# xmos_avb_brd_V4.net
KiCad netlist of a schematic drawn in EAGLE
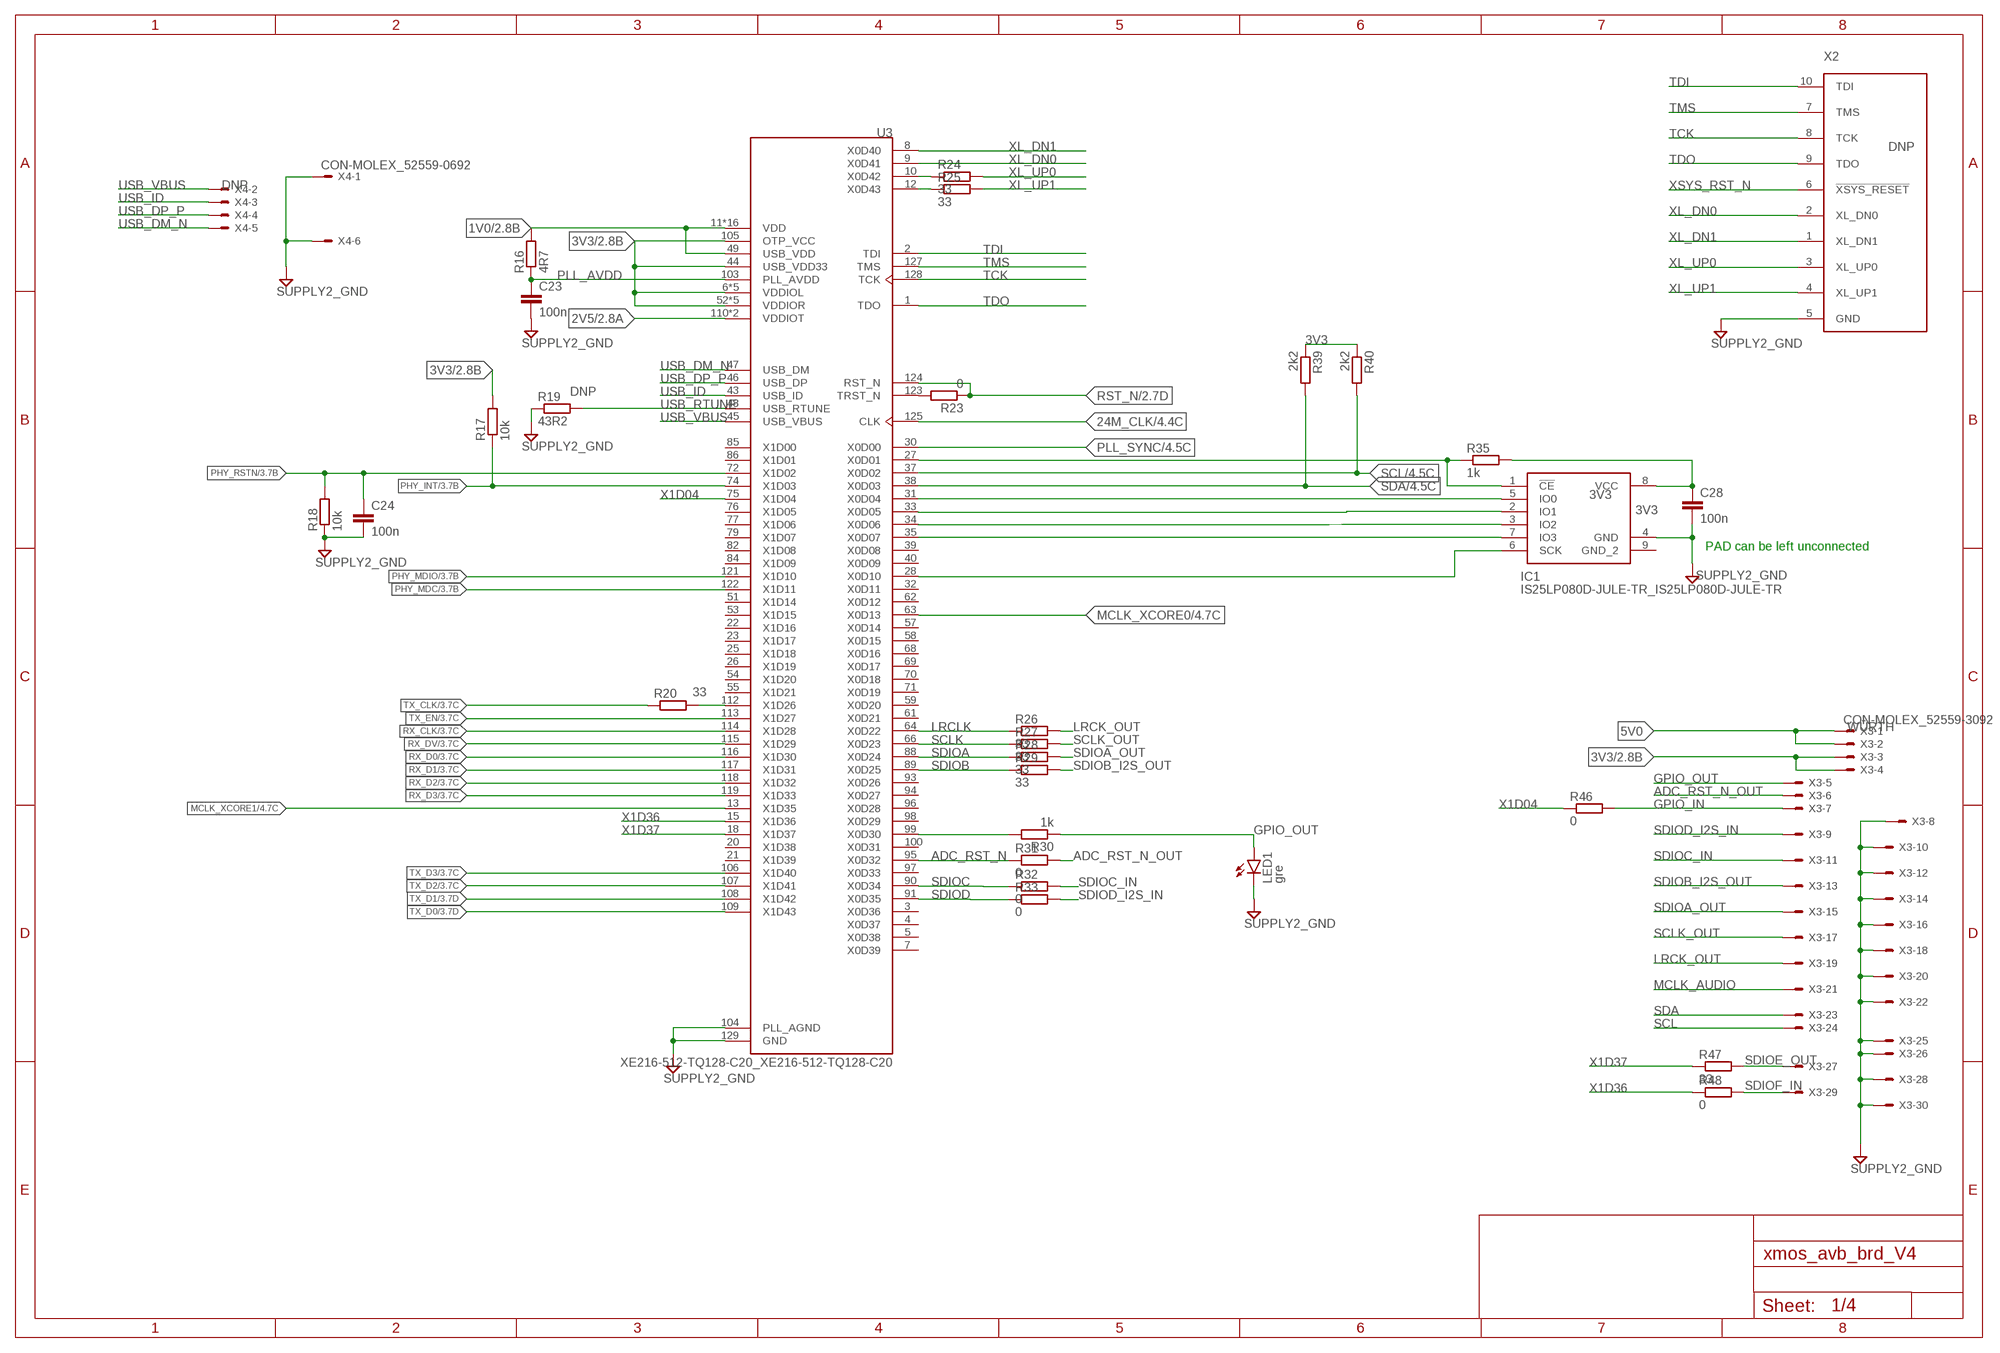
[diagram p0: schematic, sheet 1]
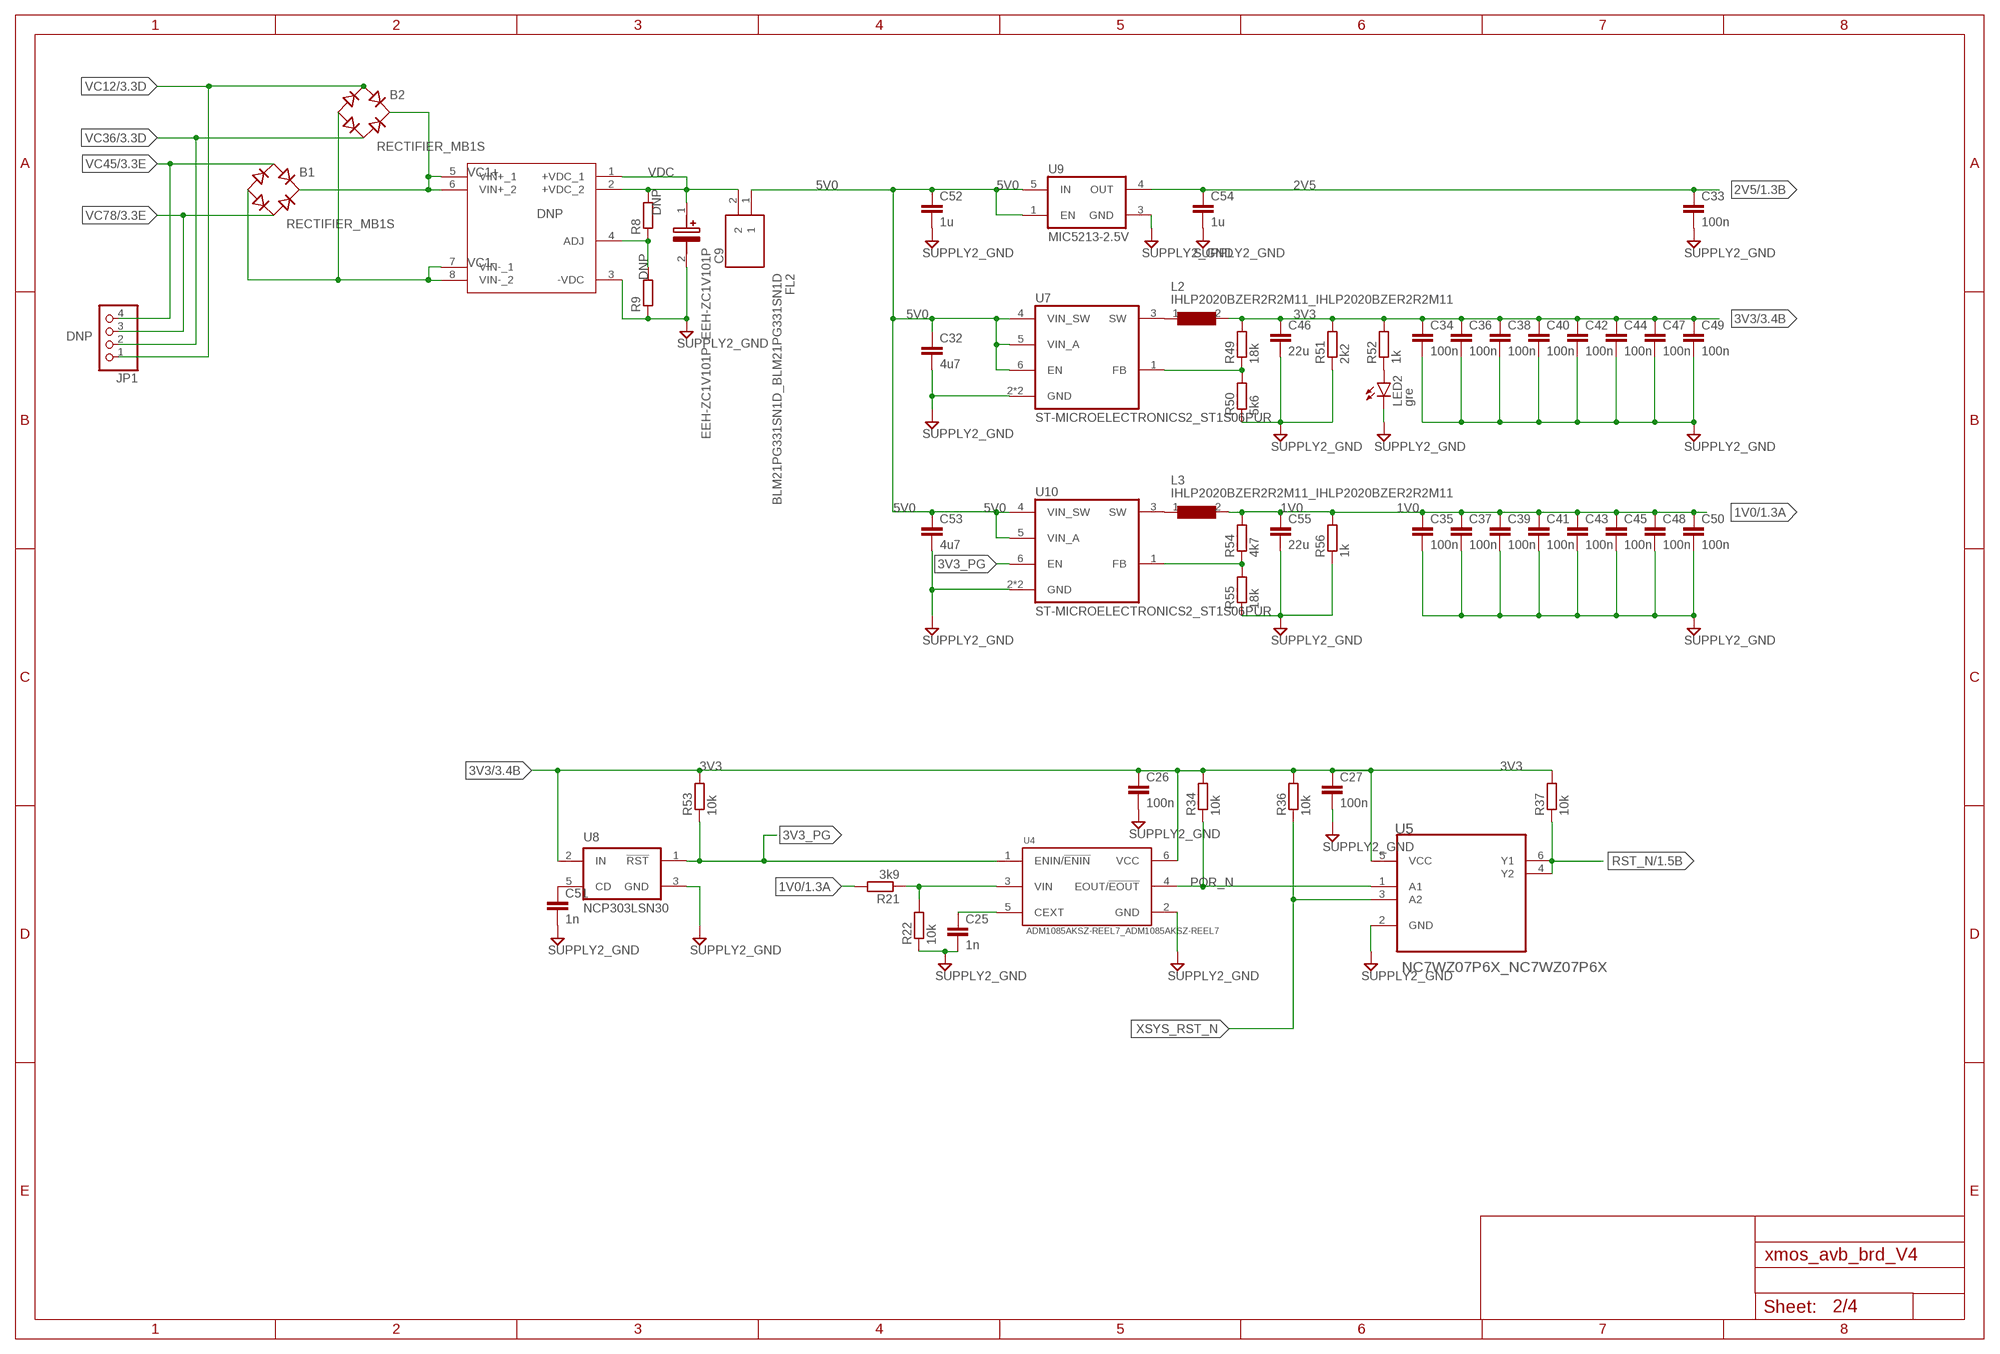
[diagram p1: schematic, sheet 2]
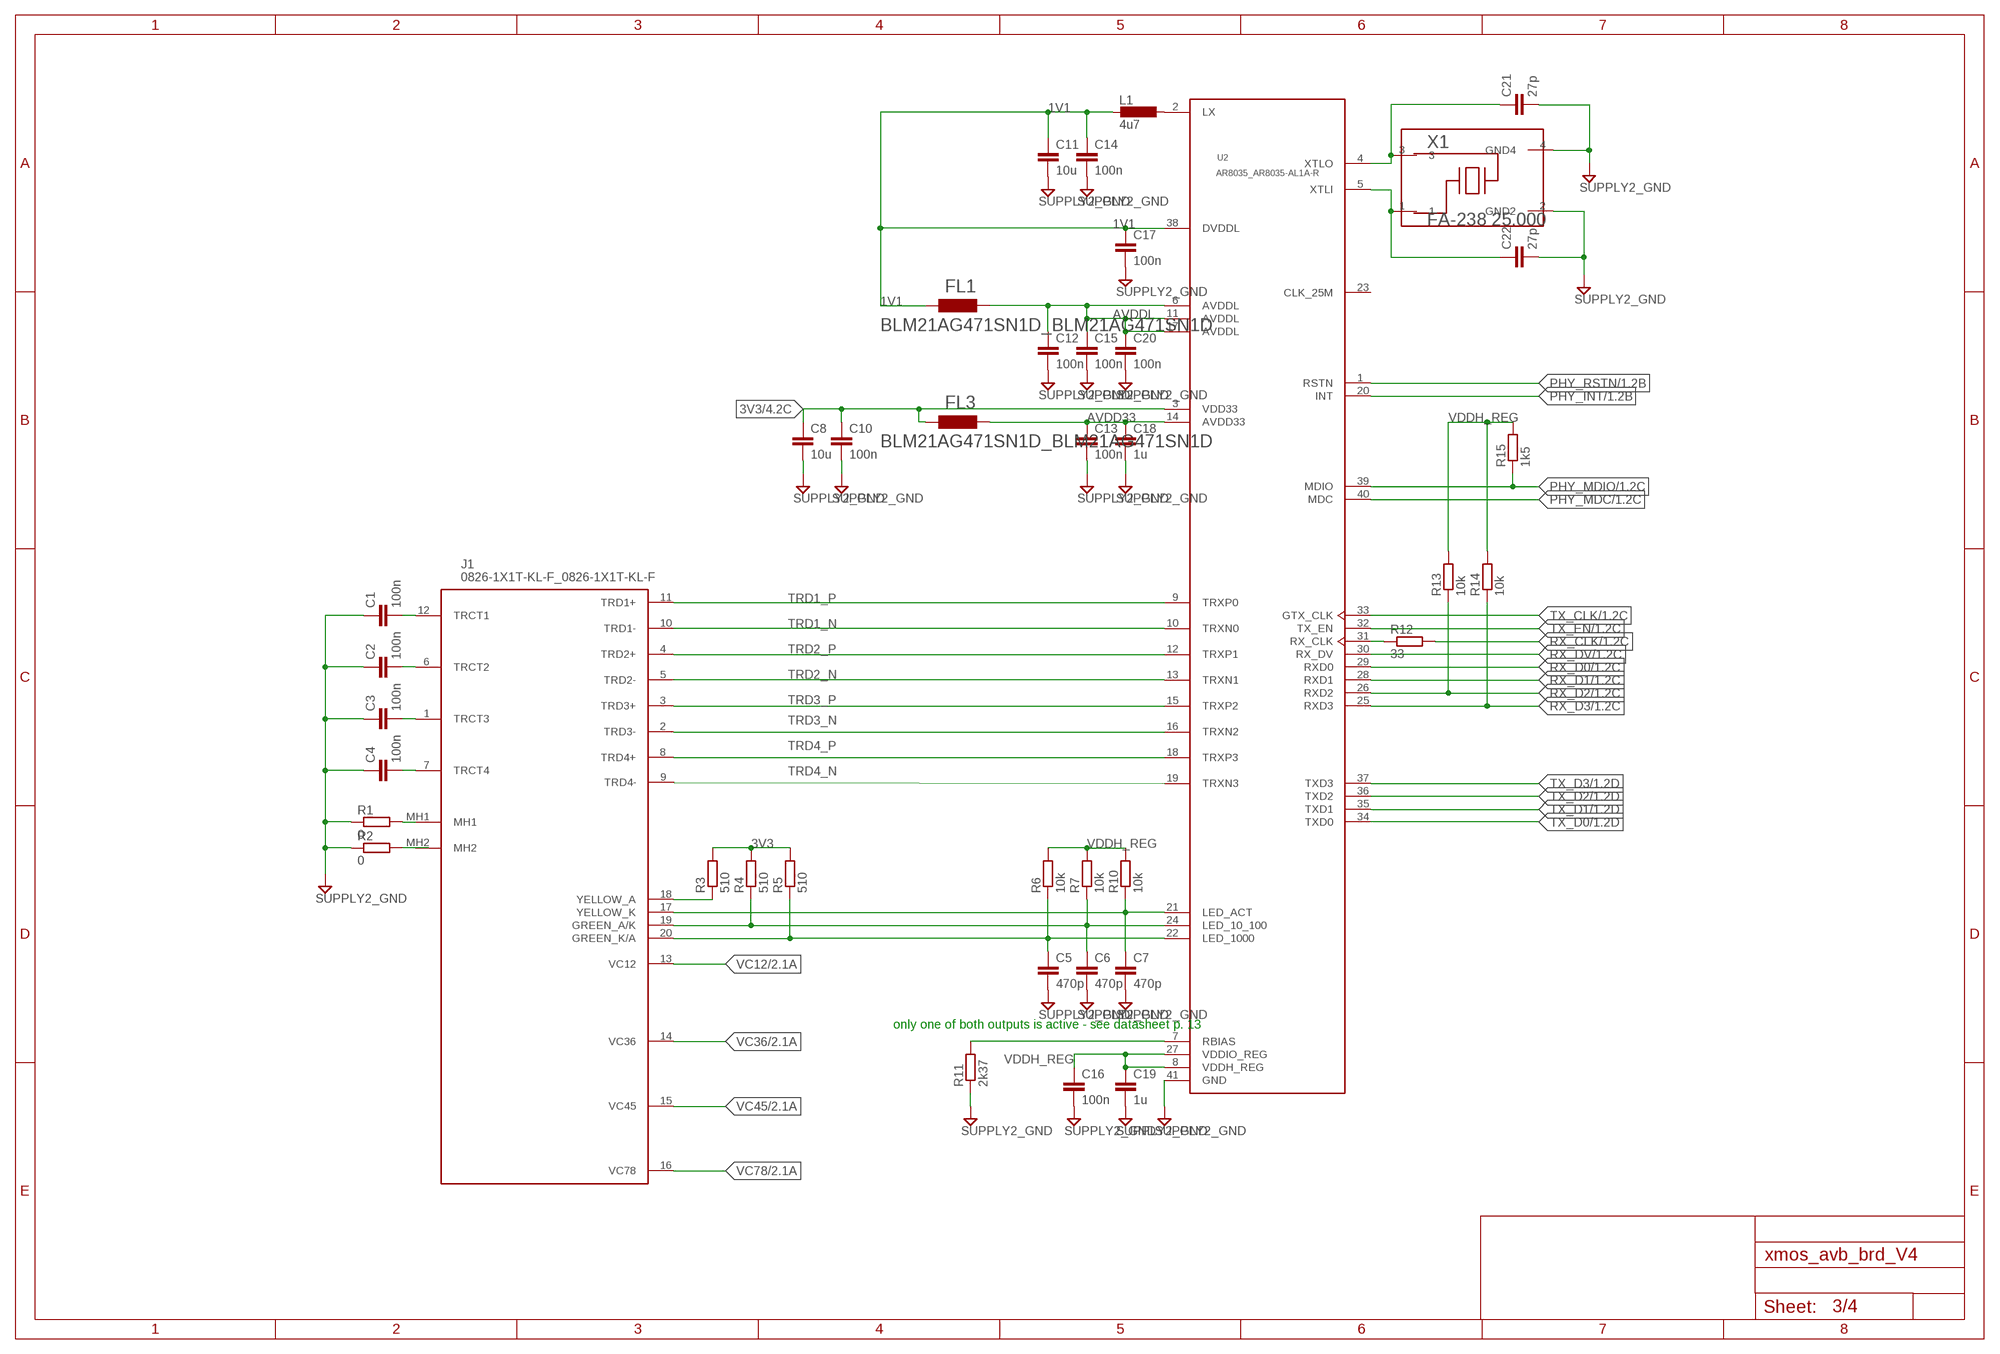
[diagram p2: schematic, sheet 3]
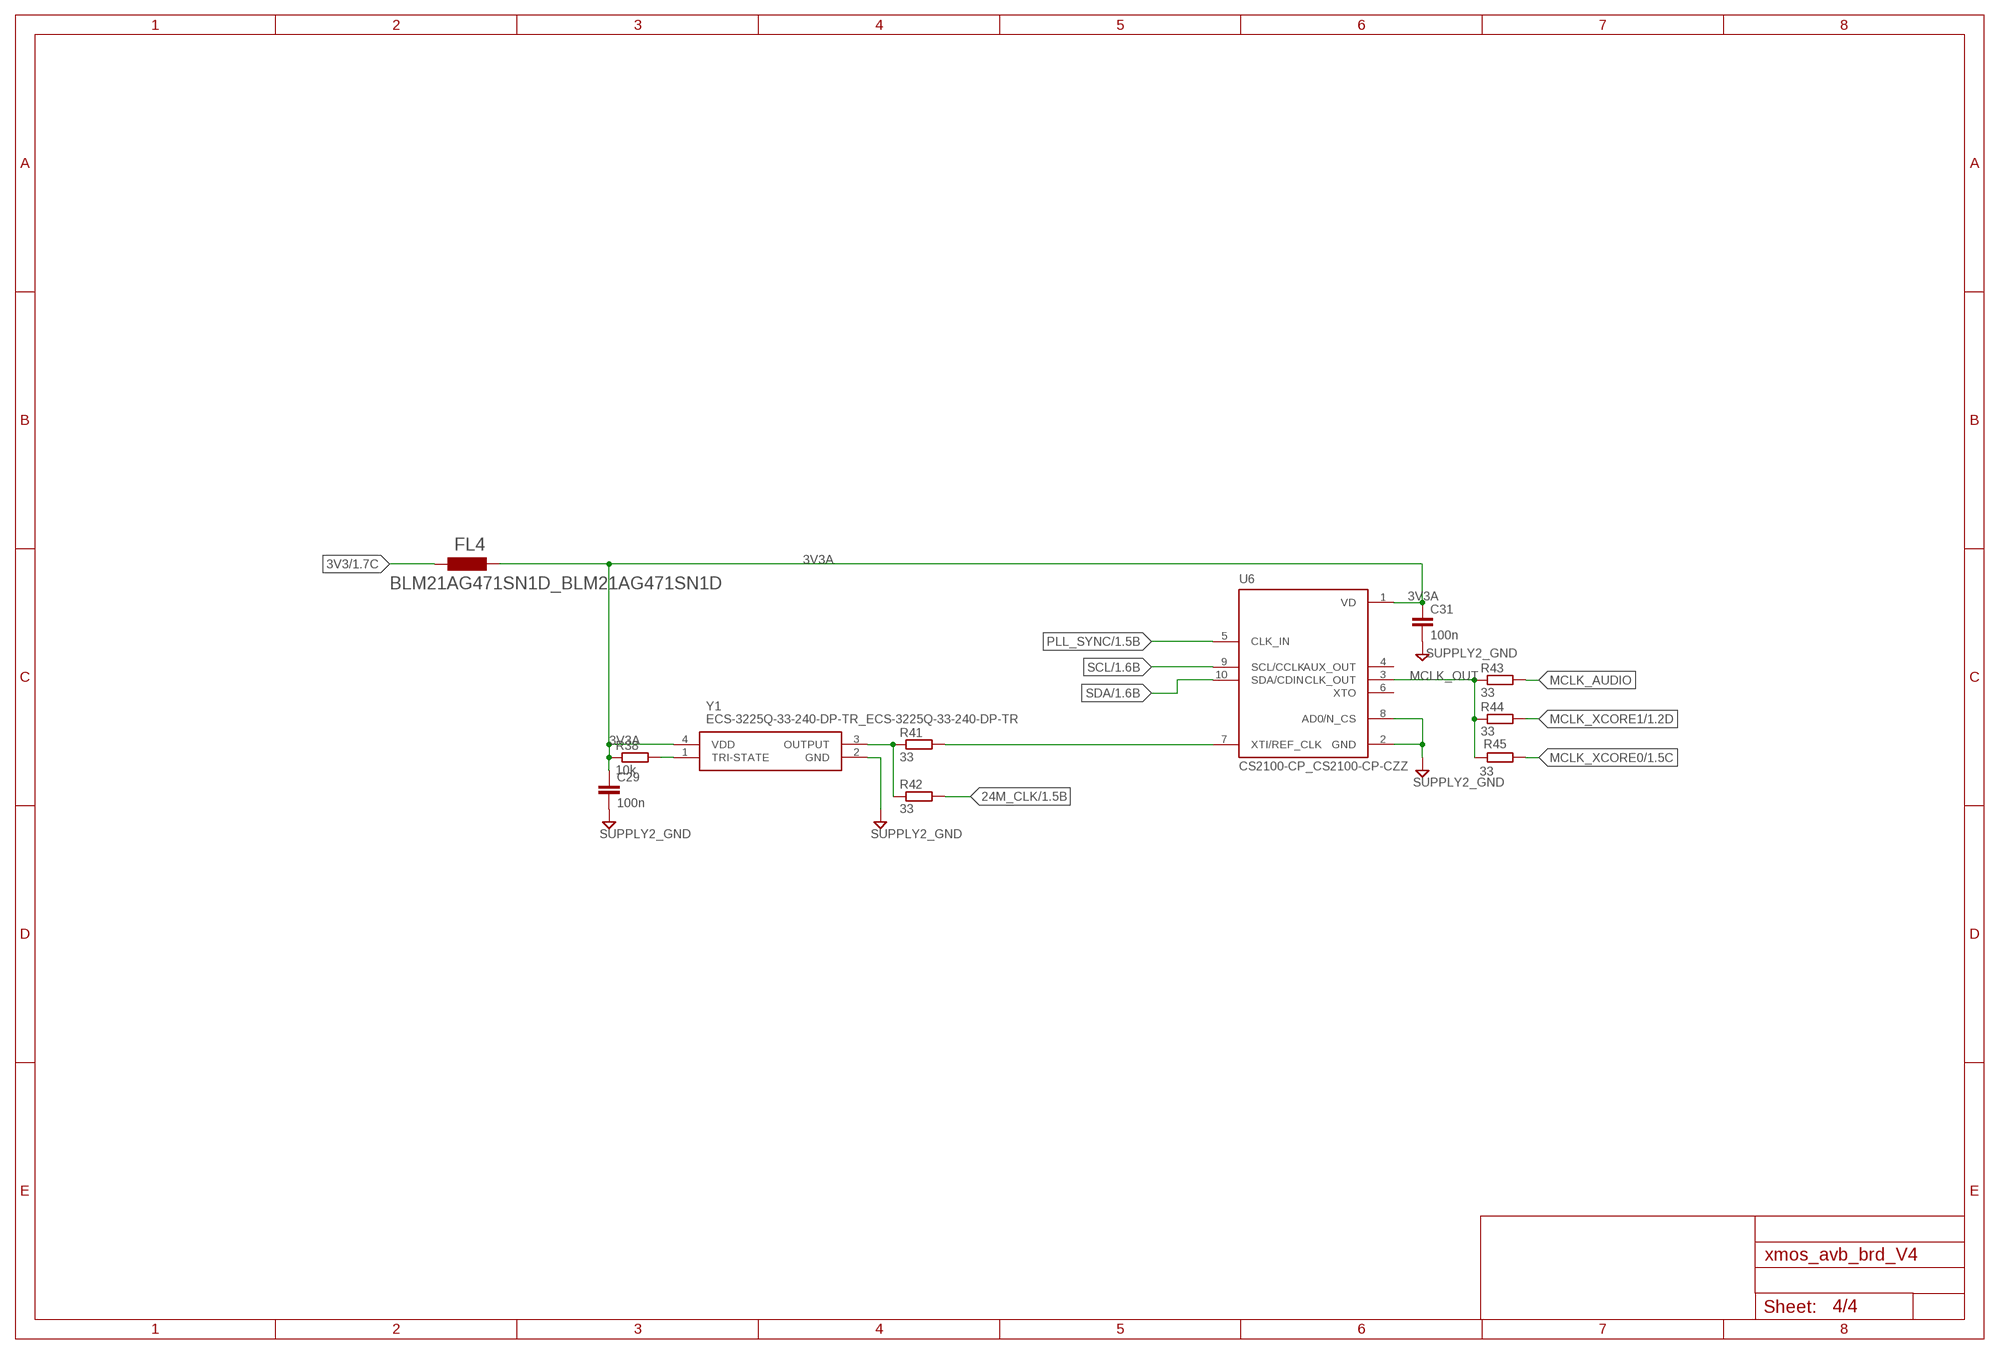
[diagram p3: schematic, sheet 4]

(export (version "E")
  (design (tool "Eeschema 10.0.6"))
  (components
    (comp (ref "C29")
      (value "100n")
      (footprint "eagle-import:RCL_C0402")
      (libsource (lib "eagle-import") (part "RCL_C-EUC0402"))
    )
    (comp (ref "C31")
      (value "100n")
      (footprint "eagle-import:RCL_C0402")
      (libsource (lib "eagle-import") (part "RCL_C-EUC0402"))
    )
    (comp (ref "FL4")
      (value "BLM21AG471SN1D_BLM21AG471SN1D")
      (footprint "eagle-import:BLM21AG471SN1D_BEADC2012X105N")
      (fields (field (name "MF") "Murata Electronics") (field (name "MP") "BLM21AG471SN1D"))
      (libsource (lib "eagle-import") (part "BLM21AG471SN1D_BLM21AG471SN1D"))
    )
    (comp (ref "R38")
      (value "10k")
      (footprint "eagle-import:RCL_R0402")
      (libsource (lib "eagle-import") (part "RCL_R-EU_R0402"))
    )
    (comp (ref "R41")
      (value "33")
      (footprint "eagle-import:RCL_R0402")
      (libsource (lib "eagle-import") (part "RCL_R-EU_R0402"))
    )
    (comp (ref "R42")
      (value "33")
      (footprint "eagle-import:RCL_R0402")
      (libsource (lib "eagle-import") (part "RCL_R-EU_R0402"))
    )
    (comp (ref "R43")
      (value "33")
      (footprint "eagle-import:RCL_R0402")
      (libsource (lib "eagle-import") (part "RCL_R-EU_R0402"))
    )
    (comp (ref "R44")
      (value "33")
      (footprint "eagle-import:RCL_R0402")
      (libsource (lib "eagle-import") (part "RCL_R-EU_R0402"))
    )
    (comp (ref "R45")
      (value "33")
      (footprint "eagle-import:RCL_R0402")
      (libsource (lib "eagle-import") (part "RCL_R-EU_R0402"))
    )
    (comp (ref "U6")
      (value "CS2100-CP_CS2100-CP-CZZ")
      (footprint "eagle-import:CS2100-CP_CIRRUS-LOGIC_MSOP10")
      (libsource (lib "eagle-import") (part "CS2100-CP_CS2100-CP-CZZ"))
    )
    (comp (ref "Y1")
      (value "ECS-3225Q-33-240-DP-TR_ECS-3225Q-33-240-DP-TR")
      (footprint "eagle-import:ECS-3225Q-33-240-DP-TR_ECS3225Q33240DPTR")
      (fields
        (field (name "MANUFACTURER_PART_NUMBER") "ECS-3225Q-33-240-DP-TR")
        (field (name "MOUSER_PART_NUMBER") "520-3225Q-33-240-DPT")
      )
      (libsource (lib "eagle-import") (part "ECS-3225Q-33-240-DP-TR_ECS-3225Q-33-240-DP-TR"))
    )
    (comp (ref "B1")
      (value "RECTIFIER_MB1S")
      (footprint "eagle-import:RECTIFIER_SOIC-4")
      (libsource (lib "eagle-import") (part "RECTIFIER_MBS1"))
    )
    (comp (ref "B2")
      (value "RECTIFIER_MB1S")
      (footprint "eagle-import:RECTIFIER_SOIC-4")
      (libsource (lib "eagle-import") (part "RECTIFIER_MBS1"))
    )
    (comp (ref "C9")
      (value "EEH-ZC1V101P_EEH-ZC1V101P")
      (footprint "eagle-import:EEH-ZC1V101P_CAPAE830X1050N")
      (fields
        (field (name "MANUFACTURER_PART_NUMBER") "EEH-ZC1V101P")
        (field (name "MOUSER_PART_NUMBER") "667-EEH-ZC1V101P")
      )
      (libsource (lib "eagle-import") (part "EEH-ZC1V101P_EEH-ZC1V101P"))
    )
    (comp (ref "C25")
      (value "1n")
      (footprint "eagle-import:RCL_C0402")
      (libsource (lib "eagle-import") (part "RCL_C-EUC0402"))
    )
    (comp (ref "C26")
      (value "100n")
      (footprint "eagle-import:RCL_C0402")
      (libsource (lib "eagle-import") (part "RCL_C-EUC0402"))
    )
    (comp (ref "C27")
      (value "100n")
      (footprint "eagle-import:RCL_C0402")
      (libsource (lib "eagle-import") (part "RCL_C-EUC0402"))
    )
    (comp (ref "C32")
      (value "4u7")
      (footprint "eagle-import:RCL_C1206")
      (libsource (lib "eagle-import") (part "RCL_C-EUC1206"))
    )
    (comp (ref "C33")
      (value "100n")
      (footprint "eagle-import:RCL_C0402")
      (libsource (lib "eagle-import") (part "RCL_C-EUC0402"))
    )
    (comp (ref "C34")
      (value "100n")
      (footprint "eagle-import:RCL_C0402")
      (libsource (lib "eagle-import") (part "RCL_C-EUC0402"))
    )
    (comp (ref "C35")
      (value "100n")
      (footprint "eagle-import:RCL_C0402")
      (libsource (lib "eagle-import") (part "RCL_C-EUC0402"))
    )
    (comp (ref "C36")
      (value "100n")
      (footprint "eagle-import:RCL_C0402")
      (libsource (lib "eagle-import") (part "RCL_C-EUC0402"))
    )
    (comp (ref "C37")
      (value "100n")
      (footprint "eagle-import:RCL_C0402")
      (libsource (lib "eagle-import") (part "RCL_C-EUC0402"))
    )
    (comp (ref "C38")
      (value "100n")
      (footprint "eagle-import:RCL_C0402")
      (libsource (lib "eagle-import") (part "RCL_C-EUC0402"))
    )
    (comp (ref "C39")
      (value "100n")
      (footprint "eagle-import:RCL_C0402")
      (libsource (lib "eagle-import") (part "RCL_C-EUC0402"))
    )
    (comp (ref "C40")
      (value "100n")
      (footprint "eagle-import:RCL_C0402")
      (libsource (lib "eagle-import") (part "RCL_C-EUC0402"))
    )
    (comp (ref "C41")
      (value "100n")
      (footprint "eagle-import:RCL_C0402")
      (libsource (lib "eagle-import") (part "RCL_C-EUC0402"))
    )
    (comp (ref "C42")
      (value "100n")
      (footprint "eagle-import:RCL_C0402")
      (libsource (lib "eagle-import") (part "RCL_C-EUC0402"))
    )
    (comp (ref "C43")
      (value "100n")
      (footprint "eagle-import:RCL_C0402")
      (libsource (lib "eagle-import") (part "RCL_C-EUC0402"))
    )
    (comp (ref "C44")
      (value "100n")
      (footprint "eagle-import:RCL_C0402")
      (libsource (lib "eagle-import") (part "RCL_C-EUC0402"))
    )
    (comp (ref "C45")
      (value "100n")
      (footprint "eagle-import:RCL_C0402")
      (libsource (lib "eagle-import") (part "RCL_C-EUC0402"))
    )
    (comp (ref "C46")
      (value "22u")
      (footprint "eagle-import:RCL_C1206")
      (libsource (lib "eagle-import") (part "RCL_C-EUC1206"))
    )
    (comp (ref "C47")
      (value "100n")
      (footprint "eagle-import:RCL_C0402")
      (libsource (lib "eagle-import") (part "RCL_C-EUC0402"))
    )
    (comp (ref "C48")
      (value "100n")
      (footprint "eagle-import:RCL_C0402")
      (libsource (lib "eagle-import") (part "RCL_C-EUC0402"))
    )
    (comp (ref "C49")
      (value "100n")
      (footprint "eagle-import:RCL_C0402")
      (libsource (lib "eagle-import") (part "RCL_C-EUC0402"))
    )
    (comp (ref "C50")
      (value "100n")
      (footprint "eagle-import:RCL_C0402")
      (libsource (lib "eagle-import") (part "RCL_C-EUC0402"))
    )
    (comp (ref "C51")
      (value "1n")
      (footprint "eagle-import:RCL_C0402")
      (libsource (lib "eagle-import") (part "RCL_C-EUC0402"))
    )
    (comp (ref "C52")
      (value "1u")
      (footprint "eagle-import:RCL_C1206")
      (libsource (lib "eagle-import") (part "RCL_C-EUC1206"))
    )
    (comp (ref "C53")
      (value "4u7")
      (footprint "eagle-import:RCL_C1206")
      (libsource (lib "eagle-import") (part "RCL_C-EUC1206"))
    )
    (comp (ref "C54")
      (value "1u")
      (footprint "eagle-import:RCL_C1206")
      (libsource (lib "eagle-import") (part "RCL_C-EUC1206"))
    )
    (comp (ref "C55")
      (value "22u")
      (footprint "eagle-import:RCL_C1206")
      (libsource (lib "eagle-import") (part "RCL_C-EUC1206"))
    )
    (comp (ref "FL2")
      (value "BLM21PG331SN1D_BLM21PG331SN1D")
      (footprint "eagle-import:BLM21PG331SN1D_BEADC2012X105N")
      (fields
        (field (name "MANUFACTURER_PART_NUMBER") "BLM21PG331SN1D")
        (field (name "MOUSER_PART_NUMBER") "81-BLM21P331SG")
      )
      (libsource (lib "eagle-import") (part "BLM21PG331SN1D_BLM21PG331SN1D"))
    )
    (comp (ref "JP1")
      (value "PINHEAD_PINHD-1X4")
      (footprint "eagle-import:PINHEAD_1X04")
      (fields (field (name "DNP") "DNP"))
      (libsource (lib "eagle-import") (part "PINHEAD_PINHD-1X4"))
    )
    (comp (ref "L2")
      (value "IHLP2020BZER2R2M11_IHLP2020BZER2R2M11")
      (footprint "eagle-import:IHLP2020BZER2R2M11_INDPM5552X200N")
      (fields
        (field (name "MANUFACTURER_PART_NUMBER") "IHLP2020BZER2R2M11")
        (field (name "MOUSER_PART_NUMBER") "70-IHLP2020BZER2R2M1")
      )
      (libsource (lib "eagle-import") (part "IHLP2020BZER2R2M11_IHLP2020BZER2R2M11"))
    )
    (comp (ref "L3")
      (value "IHLP2020BZER2R2M11_IHLP2020BZER2R2M11")
      (footprint "eagle-import:IHLP2020BZER2R2M11_INDPM5552X200N")
      (fields
        (field (name "MANUFACTURER_PART_NUMBER") "IHLP2020BZER2R2M11")
        (field (name "MOUSER_PART_NUMBER") "70-IHLP2020BZER2R2M1")
      )
      (libsource (lib "eagle-import") (part "IHLP2020BZER2R2M11_IHLP2020BZER2R2M11"))
    )
    (comp (ref "LED2")
      (value "gre")
      (footprint "eagle-import:LED_CHIP-LED0603")
      (libsource (lib "eagle-import") (part "LED_LEDCHIP-LED0603"))
    )
    (comp (ref "R8")
      (value "RCL_R-EU_R0402")
      (footprint "eagle-import:RCL_R0402")
      (fields (field (name "DNP") "DNP"))
      (libsource (lib "eagle-import") (part "RCL_R-EU_R0402"))
    )
    (comp (ref "R9")
      (value "RCL_R-EU_R0402")
      (footprint "eagle-import:RCL_R0402")
      (fields (field (name "DNP") "DNP"))
      (libsource (lib "eagle-import") (part "RCL_R-EU_R0402"))
    )
    (comp (ref "R21")
      (value "3k9")
      (footprint "eagle-import:RCL_R0402")
      (libsource (lib "eagle-import") (part "RCL_R-EU_R0402"))
    )
    (comp (ref "R22")
      (value "10k")
      (footprint "eagle-import:RCL_R0402")
      (libsource (lib "eagle-import") (part "RCL_R-EU_R0402"))
    )
    (comp (ref "R34")
      (value "10k")
      (footprint "eagle-import:RCL_R0402")
      (libsource (lib "eagle-import") (part "RCL_R-EU_R0402"))
    )
    (comp (ref "R36")
      (value "10k")
      (footprint "eagle-import:RCL_R0402")
      (libsource (lib "eagle-import") (part "RCL_R-EU_R0402"))
    )
    (comp (ref "R37")
      (value "10k")
      (footprint "eagle-import:RCL_R0402")
      (libsource (lib "eagle-import") (part "RCL_R-EU_R0402"))
    )
    (comp (ref "R49")
      (value "18k")
      (footprint "eagle-import:RCL_R0402")
      (libsource (lib "eagle-import") (part "RCL_R-EU_R0402"))
    )
    (comp (ref "R50")
      (value "5k6")
      (footprint "eagle-import:RCL_R0402")
      (libsource (lib "eagle-import") (part "RCL_R-EU_R0402"))
    )
    (comp (ref "R51")
      (value "2k2")
      (footprint "eagle-import:RCL_R0402")
      (libsource (lib "eagle-import") (part "RCL_R-EU_R0402"))
    )
    (comp (ref "R52")
      (value "1k")
      (footprint "eagle-import:RCL_R0402")
      (libsource (lib "eagle-import") (part "RCL_R-EU_R0402"))
    )
    (comp (ref "R53")
      (value "10k")
      (footprint "eagle-import:RCL_R0402")
      (libsource (lib "eagle-import") (part "RCL_R-EU_R0402"))
    )
    (comp (ref "R54")
      (value "4k7")
      (footprint "eagle-import:RCL_R0402")
      (libsource (lib "eagle-import") (part "RCL_R-EU_R0402"))
    )
    (comp (ref "R55")
      (value "18k")
      (footprint "eagle-import:RCL_R0402")
      (libsource (lib "eagle-import") (part "RCL_R-EU_R0402"))
    )
    (comp (ref "R56")
      (value "1k")
      (footprint "eagle-import:RCL_R0402")
      (libsource (lib "eagle-import") (part "RCL_R-EU_R0402"))
    )
    (comp (ref "U1")
      (value "AG9900_AG9905LP")
      (footprint "eagle-import:AG9900_AG9900LP")
      (fields (field (name "MF") "Silvertel") (field (name "MP") "AG9905LP") (field (name "DNP") "DNP"))
      (libsource (lib "eagle-import") (part "AG9900_AG9905LP"))
    )
    (comp (ref "U4")
      (value "ADM1085AKSZ-REEL7_ADM1085AKSZ-REEL7")
      (footprint "eagle-import:ADM1085AKSZ-REEL7_SOP65P210X95-6N")
      (fields (field (name "MF") "Analog Devices") (field (name "MP") "ADM1085AKSZ-REEL7"))
      (libsource (lib "eagle-import") (part "ADM1085AKSZ-REEL7_ADM1085AKSZ-REEL7"))
    )
    (comp (ref "U5")
      (value "NC7WZ07P6X_NC7WZ07P6X")
      (footprint "eagle-import:NC7WZ07P6X_SOT65P210X110-6N")
      (fields (field (name "MF") "ON Semiconductor") (field (name "MP") "NC7WZ07P6X"))
      (libsource (lib "eagle-import") (part "NC7WZ07P6X_NC7WZ07P6X"))
    )
    (comp (ref "U7")
      (value "ST-MICROELECTRONICS2_ST1S06PUR")
      (footprint "eagle-import:ST-MICROELECTRONICS2_DFN6")
      (libsource (lib "eagle-import") (part "ST-MICROELECTRONICS2_ST1S06PUR"))
    )
    (comp (ref "U8")
      (value "NCP303LSN30")
      (footprint "eagle-import:ON-SEMI_SOT23-5")
      (libsource (lib "eagle-import") (part "ON-SEMI_NCP303"))
    )
    (comp (ref "U9")
      (value "MIC5213-2.5V")
      (footprint "eagle-import:MICREL2_SC70-5")
      (libsource (lib "eagle-import") (part "MICREL2_MIC5213"))
    )
    (comp (ref "U10")
      (value "ST-MICROELECTRONICS2_ST1S06PUR")
      (footprint "eagle-import:ST-MICROELECTRONICS2_DFN6")
      (libsource (lib "eagle-import") (part "ST-MICROELECTRONICS2_ST1S06PUR"))
    )
    (comp (ref "C1")
      (value "100n")
      (footprint "eagle-import:RCL_C0402")
      (libsource (lib "eagle-import") (part "RCL_C-EUC0402"))
    )
    (comp (ref "C2")
      (value "100n")
      (footprint "eagle-import:RCL_C0402")
      (libsource (lib "eagle-import") (part "RCL_C-EUC0402"))
    )
    (comp (ref "C3")
      (value "100n")
      (footprint "eagle-import:RCL_C0402")
      (libsource (lib "eagle-import") (part "RCL_C-EUC0402"))
    )
    (comp (ref "C4")
      (value "100n")
      (footprint "eagle-import:RCL_C0402")
      (libsource (lib "eagle-import") (part "RCL_C-EUC0402"))
    )
    (comp (ref "C5")
      (value "470p")
      (footprint "eagle-import:RCL_C0402")
      (libsource (lib "eagle-import") (part "RCL_C-EUC0402"))
    )
    (comp (ref "C6")
      (value "470p")
      (footprint "eagle-import:RCL_C0402")
      (libsource (lib "eagle-import") (part "RCL_C-EUC0402"))
    )
    (comp (ref "C7")
      (value "470p")
      (footprint "eagle-import:RCL_C0402")
      (libsource (lib "eagle-import") (part "RCL_C-EUC0402"))
    )
    (comp (ref "C8")
      (value "10u")
      (footprint "eagle-import:RCL_C1206")
      (libsource (lib "eagle-import") (part "RCL_C-EUC1206"))
    )
    (comp (ref "C10")
      (value "100n")
      (footprint "eagle-import:RCL_C0402")
      (libsource (lib "eagle-import") (part "RCL_C-EUC0402"))
    )
    (comp (ref "C11")
      (value "10u")
      (footprint "eagle-import:RCL_C1206")
      (libsource (lib "eagle-import") (part "RCL_C-EUC1206"))
    )
    (comp (ref "C12")
      (value "100n")
      (footprint "eagle-import:RCL_C0402")
      (libsource (lib "eagle-import") (part "RCL_C-EUC0402"))
    )
    (comp (ref "C13")
      (value "100n")
      (footprint "eagle-import:RCL_C0402")
      (libsource (lib "eagle-import") (part "RCL_C-EUC0402"))
    )
    (comp (ref "C14")
      (value "100n")
      (footprint "eagle-import:RCL_C0402")
      (libsource (lib "eagle-import") (part "RCL_C-EUC0402"))
    )
    (comp (ref "C15")
      (value "100n")
      (footprint "eagle-import:RCL_C0402")
      (libsource (lib "eagle-import") (part "RCL_C-EUC0402"))
    )
    (comp (ref "C16")
      (value "100n")
      (footprint "eagle-import:RCL_C0402")
      (libsource (lib "eagle-import") (part "RCL_C-EUC0402"))
    )
    (comp (ref "C17")
      (value "100n")
      (footprint "eagle-import:RCL_C0402")
      (libsource (lib "eagle-import") (part "RCL_C-EUC0402"))
    )
    (comp (ref "C18")
      (value "1u")
      (footprint "eagle-import:RCL_C1206")
      (libsource (lib "eagle-import") (part "RCL_C-EUC1206"))
    )
    (comp (ref "C19")
      (value "1u")
      (footprint "eagle-import:RCL_C1206")
      (libsource (lib "eagle-import") (part "RCL_C-EUC1206"))
    )
    (comp (ref "C20")
      (value "100n")
      (footprint "eagle-import:RCL_C0402")
      (libsource (lib "eagle-import") (part "RCL_C-EUC0402"))
    )
    (comp (ref "C21")
      (value "27p")
      (footprint "eagle-import:RCL_C0402")
      (libsource (lib "eagle-import") (part "RCL_C-EUC0402"))
    )
    (comp (ref "C22")
      (value "27p")
      (footprint "eagle-import:RCL_C0402")
      (libsource (lib "eagle-import") (part "RCL_C-EUC0402"))
    )
    (comp (ref "FL1")
      (value "BLM21AG471SN1D_BLM21AG471SN1D")
      (footprint "eagle-import:BLM21AG471SN1D_BEADC2012X105N")
      (fields (field (name "MF") "Murata Electronics") (field (name "MP") "BLM21AG471SN1D"))
      (libsource (lib "eagle-import") (part "BLM21AG471SN1D_BLM21AG471SN1D"))
    )
    (comp (ref "FL3")
      (value "BLM21AG471SN1D_BLM21AG471SN1D")
      (footprint "eagle-import:BLM21AG471SN1D_BEADC2012X105N")
      (fields (field (name "MF") "Murata Electronics") (field (name "MP") "BLM21AG471SN1D"))
      (libsource (lib "eagle-import") (part "BLM21AG471SN1D_BLM21AG471SN1D"))
    )
    (comp (ref "J1")
      (value "0826-1X1T-KL-F_0826-1X1T-KL-F")
      (footprint "eagle-import:0826-1X1T-KL-F_08261X1TKLF")
      (fields
        (field (name "MANUFACTURER_PART_NUMBER") "0826-1X1T-KL-F")
        (field (name "MOUSER_PART_NUMBER") "530-0826-1X1T-KL-F")
      )
      (libsource (lib "eagle-import") (part "0826-1X1T-KL-F_0826-1X1T-KL-F"))
    )
    (comp (ref "L1")
      (value "4u7")
      (footprint "eagle-import:RCL_L2012C")
      (libsource (lib "eagle-import") (part "RCL_L-EUL2012C"))
    )
    (comp (ref "R1")
      (value "0")
      (footprint "eagle-import:RCL_R0402")
      (libsource (lib "eagle-import") (part "RCL_R-EU_R0402"))
    )
    (comp (ref "R2")
      (value "0")
      (footprint "eagle-import:RCL_R0402")
      (libsource (lib "eagle-import") (part "RCL_R-EU_R0402"))
    )
    (comp (ref "R3")
      (value "510")
      (footprint "eagle-import:RCL_R0402")
      (libsource (lib "eagle-import") (part "RCL_R-EU_R0402"))
    )
    (comp (ref "R4")
      (value "510")
      (footprint "eagle-import:RCL_R0402")
      (libsource (lib "eagle-import") (part "RCL_R-EU_R0402"))
    )
    (comp (ref "R5")
      (value "510")
      (footprint "eagle-import:RCL_R0402")
      (libsource (lib "eagle-import") (part "RCL_R-EU_R0402"))
    )
    (comp (ref "R6")
      (value "10k")
      (footprint "eagle-import:RCL_R0402")
      (libsource (lib "eagle-import") (part "RCL_R-EU_R0402"))
    )
    (comp (ref "R7")
      (value "10k")
      (footprint "eagle-import:RCL_R0402")
      (libsource (lib "eagle-import") (part "RCL_R-EU_R0402"))
    )
    (comp (ref "R10")
      (value "10k")
      (footprint "eagle-import:RCL_R0402")
      (libsource (lib "eagle-import") (part "RCL_R-EU_R0402"))
    )
    (comp (ref "R11")
      (value "2k37")
      (footprint "eagle-import:RCL_R0402")
      (libsource (lib "eagle-import") (part "RCL_R-EU_R0402"))
    )
    (comp (ref "R12")
      (value "33")
      (footprint "eagle-import:RCL_R0402")
      (libsource (lib "eagle-import") (part "RCL_R-EU_R0402"))
    )
    (comp (ref "R13")
      (value "10k")
      (footprint "eagle-import:RCL_R0402")
      (libsource (lib "eagle-import") (part "RCL_R-EU_R0402"))
    )
    (comp (ref "R14")
      (value "10k")
      (footprint "eagle-import:RCL_R0402")
      (libsource (lib "eagle-import") (part "RCL_R-EU_R0402"))
    )
    (comp (ref "R15")
      (value "1k5")
      (footprint "eagle-import:RCL_R0402")
      (libsource (lib "eagle-import") (part "RCL_R-EU_R0402"))
    )
    (comp (ref "U2")
      (value "AR8035_AR8035-AL1A-R")
      (footprint "eagle-import:AR8035_QFN40P500X500X75-41N")
      (fields (field (name "MF") "Qualcomm") (field (name "MP") "AR8035-AL1A-R"))
      (libsource (lib "eagle-import") (part "AR8035_AR8035-AL1A-R"))
    )
    (comp (ref "X1")
      (value "FA-238 25.000")
      (footprint "eagle-import:FA-238_OSCCC320X250X70-4N")
      (fields
        (field (name "MANUFACTURER_PART_NUMBER") "FA-238 25.0000MB-C3 ")
        (field (name "MF") "Epson")
        (field (name "MP") "FA-238")
      )
      (libsource (lib "eagle-import") (part "FA-238_FA-238"))
    )
    (comp (ref "C23")
      (value "100n")
      (footprint "eagle-import:RCL_C0402")
      (libsource (lib "eagle-import") (part "RCL_C-EUC0402"))
    )
    (comp (ref "C24")
      (value "100n")
      (footprint "eagle-import:RCL_C0402")
      (libsource (lib "eagle-import") (part "RCL_C-EUC0402"))
    )
    (comp (ref "C28")
      (value "100n")
      (footprint "eagle-import:RCL_C0402")
      (libsource (lib "eagle-import") (part "RCL_C-EUC0402"))
    )
    (comp (ref "IC1")
      (value "IS25LP080D-JULE-TR_IS25LP080D-JULE-TR")
      (footprint "eagle-import:IS25LP080D-JULE-TR_SON50P300X200X55-9N")
      (fields (field (name "MANUFACTURER_PART_NUMBER") "IS25LP080D-JULE-TR"))
      (libsource (lib "eagle-import") (part "IS25LP080D-JULE-TR_IS25LP080D-JULE-TR"))
    )
    (comp (ref "LED1")
      (value "gre")
      (footprint "eagle-import:LED_CHIP-LED0603")
      (libsource (lib "eagle-import") (part "LED_LEDCHIP-LED0603"))
    )
    (comp (ref "R16")
      (value "4R7")
      (footprint "eagle-import:RCL_R0402")
      (libsource (lib "eagle-import") (part "RCL_R-EU_R0402"))
    )
    (comp (ref "R17")
      (value "10k")
      (footprint "eagle-import:RCL_R0402")
      (libsource (lib "eagle-import") (part "RCL_R-EU_R0402"))
    )
    (comp (ref "R18")
      (value "10k")
      (footprint "eagle-import:RCL_R0402")
      (libsource (lib "eagle-import") (part "RCL_R-EU_R0402"))
    )
    (comp (ref "R19")
      (value "43R2")
      (footprint "eagle-import:RCL_R0402")
      (fields (field (name "DNP") "DNP"))
      (libsource (lib "eagle-import") (part "RCL_R-EU_R0402"))
    )
    (comp (ref "R20")
      (value "33")
      (footprint "eagle-import:RCL_R0402")
      (libsource (lib "eagle-import") (part "RCL_R-EU_R0402"))
    )
    (comp (ref "R23")
      (value "0")
      (footprint "eagle-import:RCL_R0402")
      (libsource (lib "eagle-import") (part "RCL_R-EU_R0402"))
    )
    (comp (ref "R24")
      (value "33")
      (footprint "eagle-import:RCL_R0402")
      (libsource (lib "eagle-import") (part "RCL_R-EU_R0402"))
    )
    (comp (ref "R25")
      (value "33")
      (footprint "eagle-import:RCL_R0402")
      (libsource (lib "eagle-import") (part "RCL_R-EU_R0402"))
    )
    (comp (ref "R26")
      (value "33")
      (footprint "eagle-import:RCL_R0402")
      (libsource (lib "eagle-import") (part "RCL_R-EU_R0402"))
    )
    (comp (ref "R27")
      (value "33")
      (footprint "eagle-import:RCL_R0402")
      (libsource (lib "eagle-import") (part "RCL_R-EU_R0402"))
    )
    (comp (ref "R28")
      (value "33")
      (footprint "eagle-import:RCL_R0402")
      (libsource (lib "eagle-import") (part "RCL_R-EU_R0402"))
    )
    (comp (ref "R29")
      (value "33")
      (footprint "eagle-import:RCL_R0402")
      (libsource (lib "eagle-import") (part "RCL_R-EU_R0402"))
    )
    (comp (ref "R30")
      (value "1k")
      (footprint "eagle-import:RCL_R0402")
      (libsource (lib "eagle-import") (part "RCL_R-EU_R0402"))
    )
    (comp (ref "R31")
      (value "0")
      (footprint "eagle-import:RCL_R0402")
      (libsource (lib "eagle-import") (part "RCL_R-EU_R0402"))
    )
    (comp (ref "R32")
      (value "0")
      (footprint "eagle-import:RCL_R0402")
      (libsource (lib "eagle-import") (part "RCL_R-EU_R0402"))
    )
    (comp (ref "R33")
      (value "0")
      (footprint "eagle-import:RCL_R0402")
      (libsource (lib "eagle-import") (part "RCL_R-EU_R0402"))
    )
    (comp (ref "R35")
      (value "1k")
      (footprint "eagle-import:RCL_R0402")
      (libsource (lib "eagle-import") (part "RCL_R-EU_R0402"))
    )
    (comp (ref "R39")
      (value "2k2")
      (footprint "eagle-import:RCL_R0402")
      (libsource (lib "eagle-import") (part "RCL_R-EU_R0402"))
    )
    (comp (ref "R40")
      (value "2k2")
      (footprint "eagle-import:RCL_R0402")
      (libsource (lib "eagle-import") (part "RCL_R-EU_R0402"))
    )
    (comp (ref "R46")
      (value "0")
      (footprint "eagle-import:RCL_R0402")
      (libsource (lib "eagle-import") (part "RCL_R-EU_R0402"))
    )
    (comp (ref "R47")
      (value "33")
      (footprint "eagle-import:RCL_R0402")
      (libsource (lib "eagle-import") (part "RCL_R-EU_R0402"))
    )
    (comp (ref "R48")
      (value "0")
      (footprint "eagle-import:RCL_R0402")
      (libsource (lib "eagle-import") (part "RCL_R-EU_R0402"))
    )
    (comp (ref "U3")
      (value "XE216-512-TQ128-C20_XE216-512-TQ128-C20")
      (footprint "eagle-import:XE216-512-TQ128-C20_QFP40P1600X1600X120-129N")
      (fields (field (name "MF") "XMOS") (field (name "MP") "XE216-512-TQ128-C20"))
      (libsource (lib "eagle-import") (part "XE216-512-TQ128-C20_XE216-512-TQ128-C20"))
    )
    (comp (ref "X2")
      (value "TC2050-XTAG_TC2050-NL-MCP-NL")
      (footprint "eagle-import:TC2050-XTAG_TC2030-MCP-NL")
      (fields (field (name "DNP") "DNP") (field (name "DNP_1") "DNP"))
      (libsource (lib "eagle-import") (part "TC2050-XTAG_TC2050-NL-MCP-NL"))
    )
    (comp (ref "X3")
      (value "CON-MOLEX_52559-3092")
      (footprint "eagle-import:CON-MOLEX_52559-3092")
      (fields
        (field (name "MF") "MOLEX")
        (field (name "MPN") "52559-3072")
        (field (name "MF_1") "WÜRTH")
        (field (name "MPN_1") "687330124422")
      )
      (libsource (lib "eagle-import") (part "CON-MOLEX_52559-3092"))
    )
    (comp (ref "X4")
      (value "CON-MOLEX_52559-0692")
      (footprint "eagle-import:CON-MOLEX_52559-0692")
      (fields (field (name "MF") "MOLEX") (field (name "MPN") "52559-0692") (field (name "DNP") "DNP"))
      (libsource (lib "eagle-import") (part "CON-MOLEX_52559-0692"))
    )
  )
  (nets
    (net (code "1") (name "1V0") (class "Default")
      (node (ref "C35") (pin "1") (pinfunction "1_1") (pintype "passive"))
      (node (ref "C37") (pin "1") (pinfunction "1_1") (pintype "passive"))
      (node (ref "C39") (pin "1") (pinfunction "1_1") (pintype "passive"))
      (node (ref "C41") (pin "1") (pinfunction "1_1") (pintype "passive"))
      (node (ref "C43") (pin "1") (pinfunction "1_1") (pintype "passive"))
      (node (ref "C45") (pin "1") (pinfunction "1_1") (pintype "passive"))
      (node (ref "C48") (pin "1") (pinfunction "1_1") (pintype "passive"))
      (node (ref "C50") (pin "1") (pinfunction "1_1") (pintype "passive"))
      (node (ref "C55") (pin "1") (pinfunction "1_1") (pintype "passive"))
      (node (ref "L3") (pin "2") (pinfunction "2_2") (pintype "bidirectional"))
      (node (ref "R16") (pin "2") (pinfunction "2_2") (pintype "passive"))
      (node (ref "R21") (pin "2") (pinfunction "2_2") (pintype "passive"))
      (node (ref "R54") (pin "2") (pinfunction "2_2") (pintype "passive"))
      (node (ref "R56") (pin "2") (pinfunction "2_2") (pintype "passive"))
      (node (ref "U3") (pin "101") (pinfunction "VDD_101") (pintype "power_in"))
      (node (ref "U3") (pin "102") (pinfunction "VDD_102") (pintype "power_in"))
      (node (ref "U3") (pin "11") (pinfunction "VDD_11") (pintype "power_in"))
      (node (ref "U3") (pin "120") (pinfunction "VDD_120") (pintype "power_in"))
      (node (ref "U3") (pin "126") (pinfunction "VDD_126") (pintype "power_in"))
      (node (ref "U3") (pin "16") (pinfunction "VDD_16") (pintype "power_in"))
      (node (ref "U3") (pin "17") (pinfunction "VDD_17") (pintype "power_in"))
      (node (ref "U3") (pin "24") (pinfunction "VDD_24") (pintype "power_in"))
      (node (ref "U3") (pin "36") (pinfunction "VDD_36") (pintype "power_in"))
      (node (ref "U3") (pin "41") (pinfunction "VDD_41") (pintype "power_in"))
      (node (ref "U3") (pin "49") (pinfunction "USB_VDD_49") (pintype "power_in"))
      (node (ref "U3") (pin "56") (pinfunction "VDD_56") (pintype "power_in"))
      (node (ref "U3") (pin "60") (pinfunction "VDD_60") (pintype "power_in"))
      (node (ref "U3") (pin "73") (pinfunction "VDD_73") (pintype "power_in"))
      (node (ref "U3") (pin "80") (pinfunction "VDD_80") (pintype "power_in"))
      (node (ref "U3") (pin "81") (pinfunction "VDD_81") (pintype "power_in"))
      (node (ref "U3") (pin "87") (pinfunction "VDD_87") (pintype "power_in"))
    )
    (net (code "2") (name "1V1") (class "Default")
      (node (ref "C11") (pin "1") (pinfunction "1_1") (pintype "passive"))
      (node (ref "C14") (pin "1") (pinfunction "1_1") (pintype "passive"))
      (node (ref "C17") (pin "1") (pinfunction "1_1") (pintype "passive"))
      (node (ref "FL1") (pin "1") (pinfunction "1_1") (pintype "passive"))
      (node (ref "L1") (pin "2") (pinfunction "2_2") (pintype "passive"))
      (node (ref "U2") (pin "38") (pinfunction "DVDDL_38") (pintype "power_in"))
    )
    (net (code "3") (name "2V5") (class "Default")
      (node (ref "C33") (pin "1") (pinfunction "1_1") (pintype "passive"))
      (node (ref "C54") (pin "1") (pinfunction "1_1") (pintype "passive"))
      (node (ref "U3") (pin "110") (pinfunction "VDDIOT_110") (pintype "power_in"))
      (node (ref "U3") (pin "111") (pinfunction "VDDIOT_111") (pintype "power_in"))
      (node (ref "U9") (pin "4") (pinfunction "OUT_4") (pintype "passive"))
    )
    (net (code "4") (name "3V3") (class "Default")
      (node (ref "C10") (pin "1") (pinfunction "1_1") (pintype "passive"))
      (node (ref "C26") (pin "1") (pinfunction "1_1") (pintype "passive"))
      (node (ref "C27") (pin "1") (pinfunction "1_1") (pintype "passive"))
      (node (ref "C28") (pin "1") (pinfunction "1_1") (pintype "passive"))
      (node (ref "C34") (pin "1") (pinfunction "1_1") (pintype "passive"))
      (node (ref "C36") (pin "1") (pinfunction "1_1") (pintype "passive"))
      (node (ref "C38") (pin "1") (pinfunction "1_1") (pintype "passive"))
      (node (ref "C40") (pin "1") (pinfunction "1_1") (pintype "passive"))
      (node (ref "C42") (pin "1") (pinfunction "1_1") (pintype "passive"))
      (node (ref "C44") (pin "1") (pinfunction "1_1") (pintype "passive"))
      (node (ref "C46") (pin "1") (pinfunction "1_1") (pintype "passive"))
      (node (ref "C47") (pin "1") (pinfunction "1_1") (pintype "passive"))
      (node (ref "C49") (pin "1") (pinfunction "1_1") (pintype "passive"))
      (node (ref "C8") (pin "1") (pinfunction "1_1") (pintype "passive"))
      (node (ref "FL3") (pin "1") (pinfunction "1_1") (pintype "passive"))
      (node (ref "FL4") (pin "1") (pinfunction "1_1") (pintype "passive"))
      (node (ref "IC1") (pin "8") (pinfunction "VCC_8") (pintype "power_in"))
      (node (ref "L2") (pin "2") (pinfunction "2_2") (pintype "bidirectional"))
      (node (ref "R17") (pin "2") (pinfunction "2_2") (pintype "passive"))
      (node (ref "R3") (pin "2") (pinfunction "2_2") (pintype "passive"))
      (node (ref "R34") (pin "2") (pinfunction "2_2") (pintype "passive"))
      (node (ref "R35") (pin "2") (pinfunction "2_2") (pintype "passive"))
      (node (ref "R36") (pin "2") (pinfunction "2_2") (pintype "passive"))
      (node (ref "R37") (pin "2") (pinfunction "2_2") (pintype "passive"))
      (node (ref "R39") (pin "1") (pinfunction "1_1") (pintype "passive"))
      (node (ref "R4") (pin "2") (pinfunction "2_2") (pintype "passive"))
      (node (ref "R40") (pin "1") (pinfunction "1_1") (pintype "passive"))
      (node (ref "R49") (pin "2") (pinfunction "2_2") (pintype "passive"))
      (node (ref "R5") (pin "2") (pinfunction "2_2") (pintype "passive"))
      (node (ref "R51") (pin "2") (pinfunction "2_2") (pintype "passive"))
      (node (ref "R52") (pin "2") (pinfunction "2_2") (pintype "passive"))
      (node (ref "R53") (pin "2") (pinfunction "2_2") (pintype "passive"))
      (node (ref "U2") (pin "3") (pinfunction "VDD33_3") (pintype "power_in"))
      (node (ref "U3") (pin "105") (pinfunction "OTP_VCC_105") (pintype "power_in"))
      (node (ref "U3") (pin "14") (pinfunction "VDDIOL_14") (pintype "power_in"))
      (node (ref "U3") (pin "19") (pinfunction "VDDIOL_19") (pintype "power_in"))
      (node (ref "U3") (pin "29") (pinfunction "VDDIOL_29") (pintype "power_in"))
      (node (ref "U3") (pin "42") (pinfunction "VDDIOL_42") (pintype "power_in"))
      (node (ref "U3") (pin "44") (pinfunction "USB_VDD33_44") (pintype "power_in"))
      (node (ref "U3") (pin "52") (pinfunction "VDDIOR_52") (pintype "power_in"))
      (node (ref "U3") (pin "6") (pinfunction "VDDIOL_6") (pintype "power_in"))
      (node (ref "U3") (pin "67") (pinfunction "VDDIOR_67") (pintype "power_in"))
      (node (ref "U3") (pin "78") (pinfunction "VDDIOR_78") (pintype "power_in"))
      (node (ref "U3") (pin "83") (pinfunction "VDDIOR_83") (pintype "power_in"))
      (node (ref "U3") (pin "92") (pinfunction "VDDIOR_92") (pintype "power_in"))
      (node (ref "U4") (pin "6") (pinfunction "VCC_6") (pintype "power_in"))
      (node (ref "U5") (pin "5") (pinfunction "VCC_5") (pintype "power_in"))
      (node (ref "U8") (pin "2") (pinfunction "IN_2") (pintype "input"))
      (node (ref "X3") (pin "3") (pinfunction "S_3") (pintype "passive"))
      (node (ref "X3") (pin "4") (pinfunction "S_4") (pintype "passive"))
    )
    (net (code "5") (name "3V3A") (class "Default")
      (node (ref "C29") (pin "1") (pinfunction "1_1") (pintype "passive"))
      (node (ref "C31") (pin "1") (pinfunction "1_1") (pintype "passive"))
      (node (ref "FL4") (pin "2") (pinfunction "2_2") (pintype "passive"))
      (node (ref "R38") (pin "1") (pinfunction "1_1") (pintype "passive"))
      (node (ref "U6") (pin "1") (pinfunction "VD_1") (pintype "bidirectional"))
      (node (ref "Y1") (pin "4") (pinfunction "VDD_4") (pintype "bidirectional"))
    )
    (net (code "6") (name "3V3_PG") (class "Default")
      (node (ref "R53") (pin "1") (pinfunction "1_1") (pintype "passive"))
      (node (ref "U10") (pin "6") (pinfunction "EN_6") (pintype "input"))
      (node (ref "U4") (pin "1") (pinfunction "ENIN/~{ENIN}_1") (pintype "input"))
      (node (ref "U8") (pin "1") (pinfunction "~{RST}_1") (pintype "output"))
    )
    (net (code "7") (name "5V0") (class "Default")
      (node (ref "C32") (pin "1") (pinfunction "1_1") (pintype "passive"))
      (node (ref "C52") (pin "1") (pinfunction "1_1") (pintype "passive"))
      (node (ref "C53") (pin "1") (pinfunction "1_1") (pintype "passive"))
      (node (ref "FL2") (pin "1") (pinfunction "1_1") (pintype "bidirectional"))
      (node (ref "U10") (pin "4") (pinfunction "VIN_SW_4") (pintype "input"))
      (node (ref "U10") (pin "5") (pinfunction "VIN_A_5") (pintype "input"))
      (node (ref "U7") (pin "4") (pinfunction "VIN_SW_4") (pintype "input"))
      (node (ref "U7") (pin "5") (pinfunction "VIN_A_5") (pintype "input"))
      (node (ref "U7") (pin "6") (pinfunction "EN_6") (pintype "input"))
      (node (ref "U9") (pin "1") (pinfunction "EN_1") (pintype "input"))
      (node (ref "U9") (pin "5") (pinfunction "IN_5") (pintype "input"))
      (node (ref "X3") (pin "1") (pinfunction "S_1") (pintype "passive"))
      (node (ref "X3") (pin "2") (pinfunction "S_2") (pintype "passive"))
    )
    (net (code "8") (name "24M_CLK") (class "Default")
      (node (ref "R42") (pin "2") (pinfunction "2_2") (pintype "passive"))
      (node (ref "U3") (pin "125") (pinfunction "CLK_125") (pintype "input"))
    )
    (net (code "9") (name "ADC_RST_N") (class "Default")
      (node (ref "R31") (pin "1") (pinfunction "1_1") (pintype "passive"))
      (node (ref "U3") (pin "95") (pinfunction "X0D32_95") (pintype "bidirectional"))
    )
    (net (code "10") (name "ADC_RST_N_OUT") (class "Default")
      (node (ref "R31") (pin "2") (pinfunction "2_2") (pintype "passive"))
      (node (ref "X3") (pin "6") (pinfunction "S_6") (pintype "passive"))
    )
    (net (code "11") (name "AVDD33") (class "Default")
      (node (ref "C13") (pin "1") (pinfunction "1_1") (pintype "passive"))
      (node (ref "C18") (pin "1") (pinfunction "1_1") (pintype "passive"))
      (node (ref "FL3") (pin "2") (pinfunction "2_2") (pintype "passive"))
      (node (ref "U2") (pin "14") (pinfunction "AVDD33_14") (pintype "power_in"))
    )
    (net (code "12") (name "AVDDL") (class "Default")
      (node (ref "C12") (pin "1") (pinfunction "1_1") (pintype "passive"))
      (node (ref "C15") (pin "1") (pinfunction "1_1") (pintype "passive"))
      (node (ref "C20") (pin "1") (pinfunction "1_1") (pintype "passive"))
      (node (ref "FL1") (pin "2") (pinfunction "2_2") (pintype "passive"))
      (node (ref "U2") (pin "11") (pinfunction "AVDDL_11") (pintype "power_in"))
      (node (ref "U2") (pin "17") (pinfunction "AVDDL_17") (pintype "power_in"))
      (node (ref "U2") (pin "6") (pinfunction "AVDDL_6") (pintype "power_in"))
    )
    (net (code "13") (name "GND") (class "Default")
      (node (ref "C1") (pin "1") (pinfunction "1_1") (pintype "passive"))
      (node (ref "C10") (pin "2") (pinfunction "2_2") (pintype "passive"))
      (node (ref "C11") (pin "2") (pinfunction "2_2") (pintype "passive"))
      (node (ref "C12") (pin "2") (pinfunction "2_2") (pintype "passive"))
      (node (ref "C13") (pin "2") (pinfunction "2_2") (pintype "passive"))
      (node (ref "C14") (pin "2") (pinfunction "2_2") (pintype "passive"))
      (node (ref "C15") (pin "2") (pinfunction "2_2") (pintype "passive"))
      (node (ref "C16") (pin "2") (pinfunction "2_2") (pintype "passive"))
      (node (ref "C17") (pin "2") (pinfunction "2_2") (pintype "passive"))
      (node (ref "C18") (pin "2") (pinfunction "2_2") (pintype "passive"))
      (node (ref "C19") (pin "2") (pinfunction "2_2") (pintype "passive"))
      (node (ref "C2") (pin "1") (pinfunction "1_1") (pintype "passive"))
      (node (ref "C20") (pin "2") (pinfunction "2_2") (pintype "passive"))
      (node (ref "C21") (pin "2") (pinfunction "2_2") (pintype "passive"))
      (node (ref "C22") (pin "2") (pinfunction "2_2") (pintype "passive"))
      (node (ref "C23") (pin "2") (pinfunction "2_2") (pintype "passive"))
      (node (ref "C24") (pin "2") (pinfunction "2_2") (pintype "passive"))
      (node (ref "C25") (pin "2") (pinfunction "2_2") (pintype "passive"))
      (node (ref "C26") (pin "2") (pinfunction "2_2") (pintype "passive"))
      (node (ref "C27") (pin "2") (pinfunction "2_2") (pintype "passive"))
      (node (ref "C28") (pin "2") (pinfunction "2_2") (pintype "passive"))
      (node (ref "C29") (pin "2") (pinfunction "2_2") (pintype "passive"))
      (node (ref "C3") (pin "1") (pinfunction "1_1") (pintype "passive"))
      (node (ref "C31") (pin "2") (pinfunction "2_2") (pintype "passive"))
      (node (ref "C32") (pin "2") (pinfunction "2_2") (pintype "passive"))
      (node (ref "C33") (pin "2") (pinfunction "2_2") (pintype "passive"))
      (node (ref "C34") (pin "2") (pinfunction "2_2") (pintype "passive"))
      (node (ref "C35") (pin "2") (pinfunction "2_2") (pintype "passive"))
      (node (ref "C36") (pin "2") (pinfunction "2_2") (pintype "passive"))
      (node (ref "C37") (pin "2") (pinfunction "2_2") (pintype "passive"))
      (node (ref "C38") (pin "2") (pinfunction "2_2") (pintype "passive"))
      (node (ref "C39") (pin "2") (pinfunction "2_2") (pintype "passive"))
      (node (ref "C4") (pin "1") (pinfunction "1_1") (pintype "passive"))
      (node (ref "C40") (pin "2") (pinfunction "2_2") (pintype "passive"))
      (node (ref "C41") (pin "2") (pinfunction "2_2") (pintype "passive"))
      (node (ref "C42") (pin "2") (pinfunction "2_2") (pintype "passive"))
      (node (ref "C43") (pin "2") (pinfunction "2_2") (pintype "passive"))
      (node (ref "C44") (pin "2") (pinfunction "2_2") (pintype "passive"))
      (node (ref "C45") (pin "2") (pinfunction "2_2") (pintype "passive"))
      (node (ref "C46") (pin "2") (pinfunction "2_2") (pintype "passive"))
      (node (ref "C47") (pin "2") (pinfunction "2_2") (pintype "passive"))
      (node (ref "C48") (pin "2") (pinfunction "2_2") (pintype "passive"))
      (node (ref "C49") (pin "2") (pinfunction "2_2") (pintype "passive"))
      (node (ref "C5") (pin "2") (pinfunction "2_2") (pintype "passive"))
      (node (ref "C50") (pin "2") (pinfunction "2_2") (pintype "passive"))
      (node (ref "C51") (pin "2") (pinfunction "2_2") (pintype "passive"))
      (node (ref "C52") (pin "2") (pinfunction "2_2") (pintype "passive"))
      (node (ref "C53") (pin "2") (pinfunction "2_2") (pintype "passive"))
      (node (ref "C54") (pin "2") (pinfunction "2_2") (pintype "passive"))
      (node (ref "C55") (pin "2") (pinfunction "2_2") (pintype "passive"))
      (node (ref "C6") (pin "2") (pinfunction "2_2") (pintype "passive"))
      (node (ref "C7") (pin "2") (pinfunction "2_2") (pintype "passive"))
      (node (ref "C8") (pin "2") (pinfunction "2_2") (pintype "passive"))
      (node (ref "C9") (pin "2") (pinfunction "-_2") (pintype "bidirectional"))
      (node (ref "IC1") (pin "4") (pinfunction "GND_4") (pintype "power_in"))
      (node (ref "LED1") (pin "C") (pinfunction "C_C") (pintype "passive"))
      (node (ref "LED2") (pin "C") (pinfunction "C_C") (pintype "passive"))
      (node (ref "R1") (pin "1") (pinfunction "1_1") (pintype "passive"))
      (node (ref "R11") (pin "1") (pinfunction "1_1") (pintype "passive"))
      (node (ref "R18") (pin "1") (pinfunction "1_1") (pintype "passive"))
      (node (ref "R19") (pin "1") (pinfunction "1_1") (pintype "passive"))
      (node (ref "R2") (pin "1") (pinfunction "1_1") (pintype "passive"))
      (node (ref "R22") (pin "1") (pinfunction "1_1") (pintype "passive"))
      (node (ref "R50") (pin "1") (pinfunction "1_1") (pintype "passive"))
      (node (ref "R51") (pin "1") (pinfunction "1_1") (pintype "passive"))
      (node (ref "R55") (pin "1") (pinfunction "1_1") (pintype "passive"))
      (node (ref "R56") (pin "1") (pinfunction "1_1") (pintype "passive"))
      (node (ref "R9") (pin "1") (pinfunction "1_1") (pintype "passive"))
      (node (ref "U1") (pin "3") (pinfunction "-VDC_3") (pintype "bidirectional"))
      (node (ref "U10") (pin "2") (pinfunction "GND_2") (pintype "power_in"))
      (node (ref "U10") (pin "7") (pinfunction "GND_7") (pintype "power_in"))
      (node (ref "U2") (pin "41") (pinfunction "GND_41") (pintype "power_in"))
      (node (ref "U3") (pin "104") (pinfunction "PLL_AGND_104") (pintype "power_in"))
      (node (ref "U3") (pin "129") (pinfunction "GND_129") (pintype "power_in"))
      (node (ref "U4") (pin "2") (pinfunction "GND_2") (pintype "power_in"))
      (node (ref "U5") (pin "2") (pinfunction "GND_2") (pintype "passive"))
      (node (ref "U6") (pin "2") (pinfunction "GND_2") (pintype "bidirectional"))
      (node (ref "U6") (pin "8") (pinfunction "AD0/N_CS_8") (pintype "bidirectional"))
      (node (ref "U7") (pin "2") (pinfunction "GND_2") (pintype "power_in"))
      (node (ref "U7") (pin "7") (pinfunction "GND_7") (pintype "power_in"))
      (node (ref "U8") (pin "3") (pinfunction "GND_3") (pintype "input"))
      (node (ref "U9") (pin "3") (pinfunction "GND_3") (pintype "power_in"))
      (node (ref "X1") (pin "2") (pinfunction "GND2_2") (pintype "passive"))
      (node (ref "X1") (pin "4") (pinfunction "GND4_4") (pintype "passive"))
      (node (ref "X2") (pin "5") (pinfunction "GND_5") (pintype "bidirectional"))
      (node (ref "X3") (pin "10") (pinfunction "S_10") (pintype "passive"))
      (node (ref "X3") (pin "12") (pinfunction "S_12") (pintype "passive"))
      (node (ref "X3") (pin "14") (pinfunction "S_14") (pintype "passive"))
      (node (ref "X3") (pin "16") (pinfunction "S_16") (pintype "passive"))
      (node (ref "X3") (pin "18") (pinfunction "S_18") (pintype "passive"))
      (node (ref "X3") (pin "20") (pinfunction "S_20") (pintype "passive"))
      (node (ref "X3") (pin "22") (pinfunction "S_22") (pintype "passive"))
      (node (ref "X3") (pin "25") (pinfunction "S_25") (pintype "passive"))
      (node (ref "X3") (pin "26") (pinfunction "S_26") (pintype "passive"))
      (node (ref "X3") (pin "28") (pinfunction "S_28") (pintype "passive"))
      (node (ref "X3") (pin "30") (pinfunction "S_30") (pintype "passive"))
      (node (ref "X3") (pin "8") (pinfunction "S_8") (pintype "passive"))
      (node (ref "X4") (pin "1") (pinfunction "S_1") (pintype "passive"))
      (node (ref "X4") (pin "6") (pinfunction "S_6") (pintype "passive"))
      (node (ref "Y1") (pin "2") (pinfunction "GND_2") (pintype "bidirectional"))
    )
    (net (code "14") (name "GND_2") (class "Default")
      (node (ref "IC1") (pin "9") (pinfunction "GND_2_9") (pintype "power_in"))
    )
    (net (code "15") (name "GPIO_IN") (class "Default")
      (node (ref "R46") (pin "2") (pinfunction "2_2") (pintype "passive"))
      (node (ref "X3") (pin "7") (pinfunction "S_7") (pintype "passive"))
    )
    (net (code "16") (name "GPIO_OUT") (class "Default")
      (node (ref "LED1") (pin "A") (pinfunction "A_A") (pintype "passive"))
      (node (ref "R30") (pin "1") (pinfunction "1_1") (pintype "passive"))
      (node (ref "X3") (pin "5") (pinfunction "S_5") (pintype "passive"))
    )
    (net (code "17") (name "LRCK_OUT") (class "Default")
      (node (ref "R26") (pin "2") (pinfunction "2_2") (pintype "passive"))
      (node (ref "X3") (pin "19") (pinfunction "S_19") (pintype "passive"))
    )
    (net (code "18") (name "LRCLK") (class "Default")
      (node (ref "R26") (pin "1") (pinfunction "1_1") (pintype "passive"))
      (node (ref "U3") (pin "64") (pinfunction "X0D22_64") (pintype "bidirectional"))
    )
    (net (code "19") (name "MCLK_AUDIO") (class "Default")
      (node (ref "R43") (pin "2") (pinfunction "2_2") (pintype "passive"))
      (node (ref "X3") (pin "21") (pinfunction "S_21") (pintype "passive"))
    )
    (net (code "20") (name "MCLK_OUT") (class "Default")
      (node (ref "R43") (pin "1") (pinfunction "1_1") (pintype "passive"))
      (node (ref "R44") (pin "1") (pinfunction "1_1") (pintype "passive"))
      (node (ref "R45") (pin "2") (pinfunction "2_2") (pintype "passive"))
      (node (ref "U6") (pin "3") (pinfunction "CLK_OUT_3") (pintype "bidirectional"))
    )
    (net (code "21") (name "MCLK_XCORE0") (class "Default")
      (node (ref "R45") (pin "1") (pinfunction "1_1") (pintype "passive"))
      (node (ref "U3") (pin "63") (pinfunction "X0D13_63") (pintype "bidirectional"))
    )
    (net (code "22") (name "MCLK_XCORE1") (class "Default")
      (node (ref "R44") (pin "2") (pinfunction "2_2") (pintype "passive"))
      (node (ref "U3") (pin "13") (pinfunction "X1D35_13") (pintype "bidirectional"))
    )
    (net (code "23") (name "Net-(IC1-IO0)") (class "Default")
      (node (ref "IC1") (pin "5") (pinfunction "IO0_5") (pintype "bidirectional"))
      (node (ref "U3") (pin "31") (pinfunction "X0D04_31") (pintype "bidirectional"))
    )
    (net (code "24") (name "Net-(IC1-IO1)") (class "Default")
      (node (ref "IC1") (pin "2") (pinfunction "IO1_2") (pintype "bidirectional"))
      (node (ref "U3") (pin "33") (pinfunction "X0D05_33") (pintype "bidirectional"))
    )
    (net (code "25") (name "Net-(IC1-IO2)") (class "Default")
      (node (ref "IC1") (pin "3") (pinfunction "IO2_3") (pintype "bidirectional"))
      (node (ref "U3") (pin "34") (pinfunction "X0D06_34") (pintype "bidirectional"))
    )
    (net (code "26") (name "Net-(IC1-IO3)") (class "Default")
      (node (ref "IC1") (pin "7") (pinfunction "IO3_7") (pintype "bidirectional"))
      (node (ref "U3") (pin "35") (pinfunction "X0D07_35") (pintype "bidirectional"))
    )
    (net (code "27") (name "Net-(IC1-SCK)") (class "Default")
      (node (ref "IC1") (pin "6") (pinfunction "SCK_6") (pintype "input"))
      (node (ref "U3") (pin "28") (pinfunction "X0D10_28") (pintype "bidirectional"))
    )
    (net (code "28") (name "Net-(IC1-~{CE})") (class "Default")
      (node (ref "IC1") (pin "1") (pinfunction "~{CE}_1") (pintype "input"))
      (node (ref "R35") (pin "1") (pinfunction "1_1") (pintype "passive"))
      (node (ref "U3") (pin "27") (pinfunction "X0D01_27") (pintype "bidirectional"))
    )
    (net (code "29") (name "Net-(J1-GREEN_A{slash}K)") (class "Default")
      (node (ref "C6") (pin "1") (pinfunction "1_1") (pintype "passive"))
      (node (ref "J1") (pin "19") (pinfunction "GREEN_A/K_19") (pintype "bidirectional"))
      (node (ref "R4") (pin "1") (pinfunction "1_1") (pintype "passive"))
      (node (ref "R7") (pin "1") (pinfunction "1_1") (pintype "passive"))
      (node (ref "U2") (pin "24") (pinfunction "LED_10_100_24") (pintype "bidirectional"))
    )
    (net (code "30") (name "Net-(J1-GREEN_K{slash}A)") (class "Default")
      (node (ref "C5") (pin "1") (pinfunction "1_1") (pintype "passive"))
      (node (ref "J1") (pin "20") (pinfunction "GREEN_K/A_20") (pintype "bidirectional"))
      (node (ref "R5") (pin "1") (pinfunction "1_1") (pintype "passive"))
      (node (ref "R6") (pin "1") (pinfunction "1_1") (pintype "passive"))
      (node (ref "U2") (pin "22") (pinfunction "LED_1000_22") (pintype "bidirectional"))
    )
    (net (code "31") (name "Net-(J1-PadMH1)") (class "Default")
      (node (ref "J1") (pin "MH1") (pinfunction "MH1_MH1") (pintype "bidirectional"))
      (node (ref "R1") (pin "2") (pinfunction "2_2") (pintype "passive"))
    )
    (net (code "32") (name "Net-(J1-PadMH2)") (class "Default")
      (node (ref "J1") (pin "MH2") (pinfunction "MH2_MH2") (pintype "bidirectional"))
      (node (ref "R2") (pin "2") (pinfunction "2_2") (pintype "passive"))
    )
    (net (code "33") (name "Net-(J1-TRCT1)") (class "Default")
      (node (ref "C1") (pin "2") (pinfunction "2_2") (pintype "passive"))
      (node (ref "J1") (pin "12") (pinfunction "TRCT1_12") (pintype "bidirectional"))
    )
    (net (code "34") (name "Net-(J1-TRCT2)") (class "Default")
      (node (ref "C2") (pin "2") (pinfunction "2_2") (pintype "passive"))
      (node (ref "J1") (pin "6") (pinfunction "TRCT2_6") (pintype "bidirectional"))
    )
    (net (code "35") (name "Net-(J1-TRCT3)") (class "Default")
      (node (ref "C3") (pin "2") (pinfunction "2_2") (pintype "passive"))
      (node (ref "J1") (pin "1") (pinfunction "TRCT3_1") (pintype "bidirectional"))
    )
    (net (code "36") (name "Net-(J1-TRCT4)") (class "Default")
      (node (ref "C4") (pin "2") (pinfunction "2_2") (pintype "passive"))
      (node (ref "J1") (pin "7") (pinfunction "TRCT4_7") (pintype "bidirectional"))
    )
    (net (code "37") (name "Net-(J1-YELLOW_A)") (class "Default")
      (node (ref "J1") (pin "18") (pinfunction "YELLOW_A_18") (pintype "bidirectional"))
      (node (ref "R3") (pin "1") (pinfunction "1_1") (pintype "passive"))
    )
    (net (code "38") (name "Net-(J1-YELLOW_K)") (class "Default")
      (node (ref "C7") (pin "1") (pinfunction "1_1") (pintype "passive"))
      (node (ref "J1") (pin "17") (pinfunction "YELLOW_K_17") (pintype "bidirectional"))
      (node (ref "R10") (pin "1") (pinfunction "1_1") (pintype "passive"))
      (node (ref "U2") (pin "21") (pinfunction "LED_ACT_21") (pintype "bidirectional"))
    )
    (net (code "39") (name "Net-(LED2-PadA)") (class "Default")
      (node (ref "LED2") (pin "A") (pinfunction "A_A") (pintype "passive"))
      (node (ref "R52") (pin "1") (pinfunction "1_1") (pintype "passive"))
    )
    (net (code "40") (name "Net-(U1-ADJ)") (class "Default")
      (node (ref "R8") (pin "1") (pinfunction "1_1") (pintype "passive"))
      (node (ref "R9") (pin "2") (pinfunction "2_2") (pintype "passive"))
      (node (ref "U1") (pin "4") (pinfunction "ADJ_4") (pintype "bidirectional"))
    )
    (net (code "41") (name "Net-(U2-LX)") (class "Default")
      (node (ref "L1") (pin "1") (pinfunction "1_1") (pintype "passive"))
      (node (ref "U2") (pin "2") (pinfunction "LX_2") (pintype "output"))
    )
    (net (code "42") (name "Net-(U2-RBIAS)") (class "Default")
      (node (ref "R11") (pin "2") (pinfunction "2_2") (pintype "passive"))
      (node (ref "U2") (pin "7") (pinfunction "RBIAS_7") (pintype "output"))
    )
    (net (code "43") (name "Net-(U2-RX_CLK)") (class "Default")
      (node (ref "R12") (pin "1") (pinfunction "1_1") (pintype "passive"))
      (node (ref "U2") (pin "31") (pinfunction "RX_CLK_31") (pintype "bidirectional"))
    )
    (net (code "44") (name "Net-(U2-XTLI)") (class "Default")
      (node (ref "C22") (pin "1") (pinfunction "1_1") (pintype "passive"))
      (node (ref "U2") (pin "5") (pinfunction "XTLI_5") (pintype "input"))
      (node (ref "X1") (pin "1") (pinfunction "1_1") (pintype "passive"))
    )
    (net (code "45") (name "Net-(U2-XTLO)") (class "Default")
      (node (ref "C21") (pin "1") (pinfunction "1_1") (pintype "passive"))
      (node (ref "U2") (pin "4") (pinfunction "XTLO_4") (pintype "output"))
      (node (ref "X1") (pin "3") (pinfunction "3_3") (pintype "passive"))
    )
    (net (code "46") (name "Net-(U3-TRST_N)") (class "Default")
      (node (ref "R23") (pin "2") (pinfunction "2_2") (pintype "passive"))
      (node (ref "U3") (pin "123") (pinfunction "TRST_N_123") (pintype "input"))
    )
    (net (code "47") (name "Net-(U3-X0D30)") (class "Default")
      (node (ref "R30") (pin "2") (pinfunction "2_2") (pintype "passive"))
      (node (ref "U3") (pin "99") (pinfunction "X0D30_99") (pintype "bidirectional"))
    )
    (net (code "48") (name "Net-(U3-X0D42)") (class "Default")
      (node (ref "R24") (pin "1") (pinfunction "1_1") (pintype "passive"))
      (node (ref "U3") (pin "10") (pinfunction "X0D42_10") (pintype "bidirectional"))
    )
    (net (code "49") (name "Net-(U3-X0D43)") (class "Default")
      (node (ref "R25") (pin "1") (pinfunction "1_1") (pintype "passive"))
      (node (ref "U3") (pin "12") (pinfunction "X0D43_12") (pintype "bidirectional"))
    )
    (net (code "50") (name "Net-(U3-X1D26)") (class "Default")
      (node (ref "R20") (pin "2") (pinfunction "2_2") (pintype "passive"))
      (node (ref "U3") (pin "112") (pinfunction "X1D26_112") (pintype "bidirectional"))
    )
    (net (code "51") (name "Net-(U4-CEXT)") (class "Default")
      (node (ref "C25") (pin "1") (pinfunction "1_1") (pintype "passive"))
      (node (ref "U4") (pin "5") (pinfunction "CEXT_5") (pintype "passive"))
    )
    (net (code "52") (name "Net-(U4-VIN)") (class "Default")
      (node (ref "R21") (pin "1") (pinfunction "1_1") (pintype "passive"))
      (node (ref "R22") (pin "2") (pinfunction "2_2") (pintype "passive"))
      (node (ref "U4") (pin "3") (pinfunction "VIN_3") (pintype "input"))
    )
    (net (code "53") (name "Net-(U6-XTI{slash}REF_CLK)") (class "Default")
      (node (ref "R41") (pin "2") (pinfunction "2_2") (pintype "passive"))
      (node (ref "U6") (pin "7") (pinfunction "XTI/REF_CLK_7") (pintype "bidirectional"))
    )
    (net (code "54") (name "Net-(U7-FB)") (class "Default")
      (node (ref "R49") (pin "1") (pinfunction "1_1") (pintype "passive"))
      (node (ref "R50") (pin "2") (pinfunction "2_2") (pintype "passive"))
      (node (ref "U7") (pin "1") (pinfunction "FB_1") (pintype "input"))
    )
    (net (code "55") (name "Net-(U7-SW)") (class "Default")
      (node (ref "L2") (pin "1") (pinfunction "1_1") (pintype "bidirectional"))
      (node (ref "U7") (pin "3") (pinfunction "SW_3") (pintype "output"))
    )
    (net (code "56") (name "Net-(U8-CD)") (class "Default")
      (node (ref "C51") (pin "1") (pinfunction "1_1") (pintype "passive"))
      (node (ref "U8") (pin "5") (pinfunction "CD_5") (pintype "passive"))
    )
    (net (code "57") (name "Net-(U10-FB)") (class "Default")
      (node (ref "R54") (pin "1") (pinfunction "1_1") (pintype "passive"))
      (node (ref "R55") (pin "2") (pinfunction "2_2") (pintype "passive"))
      (node (ref "U10") (pin "1") (pinfunction "FB_1") (pintype "input"))
    )
    (net (code "58") (name "Net-(U10-SW)") (class "Default")
      (node (ref "L3") (pin "1") (pinfunction "1_1") (pintype "bidirectional"))
      (node (ref "U10") (pin "3") (pinfunction "SW_3") (pintype "output"))
    )
    (net (code "59") (name "Net-(Y1-OUTPUT)") (class "Default")
      (node (ref "R41") (pin "1") (pinfunction "1_1") (pintype "passive"))
      (node (ref "R42") (pin "1") (pinfunction "1_1") (pintype "passive"))
      (node (ref "Y1") (pin "3") (pinfunction "OUTPUT_3") (pintype "bidirectional"))
    )
    (net (code "60") (name "Net-(Y1-TRI-STATE)") (class "Default")
      (node (ref "R38") (pin "2") (pinfunction "2_2") (pintype "passive"))
      (node (ref "Y1") (pin "1") (pinfunction "TRI-STATE_1") (pintype "bidirectional"))
    )
    (net (code "61") (name "PHY_INT") (class "Default")
      (node (ref "R17") (pin "1") (pinfunction "1_1") (pintype "passive"))
      (node (ref "U2") (pin "20") (pinfunction "INT_20") (pintype "bidirectional"))
      (node (ref "U3") (pin "74") (pinfunction "X1D03_74") (pintype "bidirectional"))
    )
    (net (code "62") (name "PHY_MDC") (class "Default")
      (node (ref "U2") (pin "40") (pinfunction "MDC_40") (pintype "input"))
      (node (ref "U3") (pin "122") (pinfunction "X1D11_122") (pintype "bidirectional"))
    )
    (net (code "63") (name "PHY_MDIO") (class "Default")
      (node (ref "R15") (pin "1") (pinfunction "1_1") (pintype "passive"))
      (node (ref "U2") (pin "39") (pinfunction "MDIO_39") (pintype "bidirectional"))
      (node (ref "U3") (pin "121") (pinfunction "X1D10_121") (pintype "bidirectional"))
    )
    (net (code "64") (name "PHY_RSTN") (class "Default")
      (node (ref "C24") (pin "1") (pinfunction "1_1") (pintype "passive"))
      (node (ref "R18") (pin "2") (pinfunction "2_2") (pintype "passive"))
      (node (ref "U2") (pin "1") (pinfunction "RSTN_1") (pintype "input"))
      (node (ref "U3") (pin "72") (pinfunction "X1D02_72") (pintype "bidirectional"))
    )
    (net (code "65") (name "PLL_AVDD") (class "Default")
      (node (ref "C23") (pin "1") (pinfunction "1_1") (pintype "passive"))
      (node (ref "R16") (pin "1") (pinfunction "1_1") (pintype "passive"))
      (node (ref "U3") (pin "103") (pinfunction "PLL_AVDD_103") (pintype "power_in"))
    )
    (net (code "66") (name "PLL_SYNC") (class "Default")
      (node (ref "U3") (pin "30") (pinfunction "X0D00_30") (pintype "bidirectional"))
      (node (ref "U6") (pin "5") (pinfunction "CLK_IN_5") (pintype "bidirectional"))
    )
    (net (code "67") (name "POR_N") (class "Default")
      (node (ref "R34") (pin "1") (pinfunction "1_1") (pintype "passive"))
      (node (ref "U4") (pin "4") (pinfunction "EOUT/~{EOUT}_4") (pintype "output"))
      (node (ref "U5") (pin "1") (pinfunction "A1_1") (pintype "input"))
    )
    (net (code "68") (name "RST_N") (class "Default")
      (node (ref "R23") (pin "1") (pinfunction "1_1") (pintype "passive"))
      (node (ref "R37") (pin "1") (pinfunction "1_1") (pintype "passive"))
      (node (ref "U3") (pin "124") (pinfunction "RST_N_124") (pintype "input"))
      (node (ref "U5") (pin "4") (pinfunction "Y2_4") (pintype "output"))
      (node (ref "U5") (pin "6") (pinfunction "Y1_6") (pintype "output"))
    )
    (net (code "69") (name "RX_CLK") (class "Default")
      (node (ref "R12") (pin "2") (pinfunction "2_2") (pintype "passive"))
      (node (ref "U3") (pin "114") (pinfunction "X1D28_114") (pintype "bidirectional"))
    )
    (net (code "70") (name "RX_D0") (class "Default")
      (node (ref "U2") (pin "29") (pinfunction "RXD0_29") (pintype "bidirectional"))
      (node (ref "U3") (pin "116") (pinfunction "X1D30_116") (pintype "bidirectional"))
    )
    (net (code "71") (name "RX_D1") (class "Default")
      (node (ref "U2") (pin "28") (pinfunction "RXD1_28") (pintype "bidirectional"))
      (node (ref "U3") (pin "117") (pinfunction "X1D31_117") (pintype "bidirectional"))
    )
    (net (code "72") (name "RX_D2") (class "Default")
      (node (ref "R13") (pin "1") (pinfunction "1_1") (pintype "passive"))
      (node (ref "U2") (pin "26") (pinfunction "RXD2_26") (pintype "bidirectional"))
      (node (ref "U3") (pin "118") (pinfunction "X1D32_118") (pintype "bidirectional"))
    )
    (net (code "73") (name "RX_D3") (class "Default")
      (node (ref "R14") (pin "1") (pinfunction "1_1") (pintype "passive"))
      (node (ref "U2") (pin "25") (pinfunction "RXD3_25") (pintype "bidirectional"))
      (node (ref "U3") (pin "119") (pinfunction "X1D33_119") (pintype "bidirectional"))
    )
    (net (code "74") (name "RX_DV") (class "Default")
      (node (ref "U2") (pin "30") (pinfunction "RX_DV_30") (pintype "bidirectional"))
      (node (ref "U3") (pin "115") (pinfunction "X1D29_115") (pintype "bidirectional"))
    )
    (net (code "75") (name "SCL") (class "Default")
      (node (ref "R40") (pin "2") (pinfunction "2_2") (pintype "passive"))
      (node (ref "U3") (pin "37") (pinfunction "X0D02_37") (pintype "bidirectional"))
      (node (ref "U6") (pin "9") (pinfunction "SCL/CCLK_9") (pintype "bidirectional"))
      (node (ref "X3") (pin "24") (pinfunction "S_24") (pintype "passive"))
    )
    (net (code "76") (name "SCLK") (class "Default")
      (node (ref "R27") (pin "1") (pinfunction "1_1") (pintype "passive"))
      (node (ref "U3") (pin "66") (pinfunction "X0D23_66") (pintype "bidirectional"))
    )
    (net (code "77") (name "SCLK_OUT") (class "Default")
      (node (ref "R27") (pin "2") (pinfunction "2_2") (pintype "passive"))
      (node (ref "X3") (pin "17") (pinfunction "S_17") (pintype "passive"))
    )
    (net (code "78") (name "SDA") (class "Default")
      (node (ref "R39") (pin "2") (pinfunction "2_2") (pintype "passive"))
      (node (ref "U3") (pin "38") (pinfunction "X0D03_38") (pintype "bidirectional"))
      (node (ref "U6") (pin "10") (pinfunction "SDA/CDIN_10") (pintype "bidirectional"))
      (node (ref "X3") (pin "23") (pinfunction "S_23") (pintype "passive"))
    )
    (net (code "79") (name "SDIOA") (class "Default")
      (node (ref "R28") (pin "1") (pinfunction "1_1") (pintype "passive"))
      (node (ref "U3") (pin "88") (pinfunction "X0D24_88") (pintype "bidirectional"))
    )
    (net (code "80") (name "SDIOA_OUT") (class "Default")
      (node (ref "R28") (pin "2") (pinfunction "2_2") (pintype "passive"))
      (node (ref "X3") (pin "15") (pinfunction "S_15") (pintype "passive"))
    )
    (net (code "81") (name "SDIOB") (class "Default")
      (node (ref "R29") (pin "1") (pinfunction "1_1") (pintype "passive"))
      (node (ref "U3") (pin "89") (pinfunction "X0D25_89") (pintype "bidirectional"))
    )
    (net (code "82") (name "SDIOB_I2S_OUT") (class "Default")
      (node (ref "R29") (pin "2") (pinfunction "2_2") (pintype "passive"))
      (node (ref "X3") (pin "13") (pinfunction "S_13") (pintype "passive"))
    )
    (net (code "83") (name "SDIOC") (class "Default")
      (node (ref "R32") (pin "1") (pinfunction "1_1") (pintype "passive"))
      (node (ref "U3") (pin "90") (pinfunction "X0D34_90") (pintype "bidirectional"))
    )
    (net (code "84") (name "SDIOC_IN") (class "Default")
      (node (ref "R32") (pin "2") (pinfunction "2_2") (pintype "passive"))
      (node (ref "X3") (pin "11") (pinfunction "S_11") (pintype "passive"))
    )
    (net (code "85") (name "SDIOD") (class "Default")
      (node (ref "R33") (pin "1") (pinfunction "1_1") (pintype "passive"))
      (node (ref "U3") (pin "91") (pinfunction "X0D35_91") (pintype "bidirectional"))
    )
    (net (code "86") (name "SDIOD_I2S_IN") (class "Default")
      (node (ref "R33") (pin "2") (pinfunction "2_2") (pintype "passive"))
      (node (ref "X3") (pin "9") (pinfunction "S_9") (pintype "passive"))
    )
    (net (code "87") (name "SDIOE_OUT") (class "Default")
      (node (ref "R47") (pin "2") (pinfunction "2_2") (pintype "passive"))
      (node (ref "X3") (pin "27") (pinfunction "S_27") (pintype "passive"))
    )
    (net (code "88") (name "SDIOF_IN") (class "Default")
      (node (ref "R48") (pin "2") (pinfunction "2_2") (pintype "passive"))
      (node (ref "X3") (pin "29") (pinfunction "S_29") (pintype "passive"))
    )
    (net (code "89") (name "TCK") (class "Default")
      (node (ref "U3") (pin "128") (pinfunction "TCK_128") (pintype "input"))
      (node (ref "X2") (pin "8") (pinfunction "TCK_8") (pintype "bidirectional"))
    )
    (net (code "90") (name "TDI") (class "Default")
      (node (ref "U3") (pin "2") (pinfunction "TDI_2") (pintype "input"))
      (node (ref "X2") (pin "10") (pinfunction "TDI_10") (pintype "bidirectional"))
    )
    (net (code "91") (name "TDO") (class "Default")
      (node (ref "U3") (pin "1") (pinfunction "TDO_1") (pintype "output"))
      (node (ref "X2") (pin "9") (pinfunction "TDO_9") (pintype "bidirectional"))
    )
    (net (code "92") (name "TMS") (class "Default")
      (node (ref "U3") (pin "127") (pinfunction "TMS_127") (pintype "input"))
      (node (ref "X2") (pin "7") (pinfunction "TMS_7") (pintype "bidirectional"))
    )
    (net (code "93") (name "TRD1_N") (class "Default")
      (node (ref "J1") (pin "10") (pinfunction "TRD1-_10") (pintype "bidirectional"))
      (node (ref "U2") (pin "10") (pinfunction "TRXN0_10") (pintype "output"))
    )
    (net (code "94") (name "TRD1_P") (class "Default")
      (node (ref "J1") (pin "11") (pinfunction "TRD1+_11") (pintype "bidirectional"))
      (node (ref "U2") (pin "9") (pinfunction "TRXP0_9") (pintype "input"))
    )
    (net (code "95") (name "TRD2_N") (class "Default")
      (node (ref "J1") (pin "5") (pinfunction "TRD2-_5") (pintype "bidirectional"))
      (node (ref "U2") (pin "13") (pinfunction "TRXN1_13") (pintype "output"))
    )
    (net (code "96") (name "TRD2_P") (class "Default")
      (node (ref "J1") (pin "4") (pinfunction "TRD2+_4") (pintype "bidirectional"))
      (node (ref "U2") (pin "12") (pinfunction "TRXP1_12") (pintype "input"))
    )
    (net (code "97") (name "TRD3_N") (class "Default")
      (node (ref "J1") (pin "2") (pinfunction "TRD3-_2") (pintype "bidirectional"))
      (node (ref "U2") (pin "16") (pinfunction "TRXN2_16") (pintype "output"))
    )
    (net (code "98") (name "TRD3_P") (class "Default")
      (node (ref "J1") (pin "3") (pinfunction "TRD3+_3") (pintype "bidirectional"))
      (node (ref "U2") (pin "15") (pinfunction "TRXP2_15") (pintype "input"))
    )
    (net (code "99") (name "TRD4_N") (class "Default")
      (node (ref "J1") (pin "9") (pinfunction "TRD4-_9") (pintype "bidirectional"))
      (node (ref "U2") (pin "19") (pinfunction "TRXN3_19") (pintype "output"))
    )
    (net (code "100") (name "TRD4_P") (class "Default")
      (node (ref "J1") (pin "8") (pinfunction "TRD4+_8") (pintype "bidirectional"))
      (node (ref "U2") (pin "18") (pinfunction "TRXP3_18") (pintype "input"))
    )
    (net (code "101") (name "TX_CLK") (class "Default")
      (node (ref "R20") (pin "1") (pinfunction "1_1") (pintype "passive"))
      (node (ref "U2") (pin "33") (pinfunction "GTX_CLK_33") (pintype "input"))
    )
    (net (code "102") (name "TX_D0") (class "Default")
      (node (ref "U2") (pin "34") (pinfunction "TXD0_34") (pintype "input"))
      (node (ref "U3") (pin "109") (pinfunction "X1D43_109") (pintype "bidirectional"))
    )
    (net (code "103") (name "TX_D1") (class "Default")
      (node (ref "U2") (pin "35") (pinfunction "TXD1_35") (pintype "input"))
      (node (ref "U3") (pin "108") (pinfunction "X1D42_108") (pintype "bidirectional"))
    )
    (net (code "104") (name "TX_D2") (class "Default")
      (node (ref "U2") (pin "36") (pinfunction "TXD2_36") (pintype "input"))
      (node (ref "U3") (pin "107") (pinfunction "X1D41_107") (pintype "bidirectional"))
    )
    (net (code "105") (name "TX_D3") (class "Default")
      (node (ref "U2") (pin "37") (pinfunction "TXD3_37") (pintype "input"))
      (node (ref "U3") (pin "106") (pinfunction "X1D40_106") (pintype "bidirectional"))
    )
    (net (code "106") (name "TX_EN") (class "Default")
      (node (ref "U2") (pin "32") (pinfunction "TX_EN_32") (pintype "input"))
      (node (ref "U3") (pin "113") (pinfunction "X1D27_113") (pintype "bidirectional"))
    )
    (net (code "107") (name "USB_DM_N") (class "Default")
      (node (ref "U3") (pin "47") (pinfunction "USB_DM_47") (pintype "bidirectional"))
      (node (ref "X4") (pin "5") (pinfunction "S_5") (pintype "passive"))
    )
    (net (code "108") (name "USB_DP_P") (class "Default")
      (node (ref "U3") (pin "46") (pinfunction "USB_DP_46") (pintype "bidirectional"))
      (node (ref "X4") (pin "4") (pinfunction "S_4") (pintype "passive"))
    )
    (net (code "109") (name "USB_ID") (class "Default")
      (node (ref "U3") (pin "43") (pinfunction "USB_ID_43") (pintype "bidirectional"))
      (node (ref "X4") (pin "3") (pinfunction "S_3") (pintype "passive"))
    )
    (net (code "110") (name "USB_RTUNE") (class "Default")
      (node (ref "R19") (pin "2") (pinfunction "2_2") (pintype "passive"))
      (node (ref "U3") (pin "48") (pinfunction "USB_RTUNE_48") (pintype "bidirectional"))
    )
    (net (code "111") (name "USB_VBUS") (class "Default")
      (node (ref "U3") (pin "45") (pinfunction "USB_VBUS_45") (pintype "bidirectional"))
      (node (ref "X4") (pin "2") (pinfunction "S_2") (pintype "passive"))
    )
    (net (code "112") (name "VC1+") (class "Default")
      (node (ref "B1") (pin "+") (pinfunction "+_+") (pintype "passive"))
      (node (ref "B2") (pin "+") (pinfunction "+_+") (pintype "passive"))
      (node (ref "U1") (pin "5") (pinfunction "VIN+_1_5") (pintype "bidirectional"))
      (node (ref "U1") (pin "6") (pinfunction "VIN+_2_6") (pintype "bidirectional"))
    )
    (net (code "113") (name "VC1-") (class "Default")
      (node (ref "B1") (pin "-") (pinfunction "-_-") (pintype "passive"))
      (node (ref "B2") (pin "-") (pinfunction "-_-") (pintype "passive"))
      (node (ref "U1") (pin "7") (pinfunction "VIN-_1_7") (pintype "bidirectional"))
      (node (ref "U1") (pin "8") (pinfunction "VIN-_2_8") (pintype "bidirectional"))
    )
    (net (code "114") (name "VC12") (class "Default")
      (node (ref "B2") (pin "~1") (pinfunction "AC1_~1") (pintype "passive"))
      (node (ref "J1") (pin "13") (pinfunction "VC12_13") (pintype "bidirectional"))
      (node (ref "JP1") (pin "1") (pinfunction "1_1") (pintype "passive"))
    )
    (net (code "115") (name "VC36") (class "Default")
      (node (ref "B2") (pin "~2") (pinfunction "AC2_~2") (pintype "passive"))
      (node (ref "J1") (pin "14") (pinfunction "VC36_14") (pintype "bidirectional"))
      (node (ref "JP1") (pin "2") (pinfunction "2_2") (pintype "passive"))
    )
    (net (code "116") (name "VC45") (class "Default")
      (node (ref "B1") (pin "~1") (pinfunction "AC1_~1") (pintype "passive"))
      (node (ref "J1") (pin "15") (pinfunction "VC45_15") (pintype "bidirectional"))
      (node (ref "JP1") (pin "4") (pinfunction "4_4") (pintype "passive"))
    )
    (net (code "117") (name "VC78") (class "Default")
      (node (ref "B1") (pin "~2") (pinfunction "AC2_~2") (pintype "passive"))
      (node (ref "J1") (pin "16") (pinfunction "VC78_16") (pintype "bidirectional"))
      (node (ref "JP1") (pin "3") (pinfunction "3_3") (pintype "passive"))
    )
    (net (code "118") (name "VDC") (class "Default")
      (node (ref "C9") (pin "1") (pinfunction "+_1") (pintype "bidirectional"))
      (node (ref "FL2") (pin "2") (pinfunction "2_2") (pintype "bidirectional"))
      (node (ref "R8") (pin "2") (pinfunction "2_2") (pintype "passive"))
      (node (ref "U1") (pin "1") (pinfunction "+VDC_1_1") (pintype "bidirectional"))
      (node (ref "U1") (pin "2") (pinfunction "+VDC_2_2") (pintype "bidirectional"))
    )
    (net (code "119") (name "VDDH_REG") (class "Default")
      (node (ref "C16") (pin "1") (pinfunction "1_1") (pintype "passive"))
      (node (ref "C19") (pin "1") (pinfunction "1_1") (pintype "passive"))
      (node (ref "R10") (pin "2") (pinfunction "2_2") (pintype "passive"))
      (node (ref "R13") (pin "2") (pinfunction "2_2") (pintype "passive"))
      (node (ref "R14") (pin "2") (pinfunction "2_2") (pintype "passive"))
      (node (ref "R15") (pin "2") (pinfunction "2_2") (pintype "passive"))
      (node (ref "R6") (pin "2") (pinfunction "2_2") (pintype "passive"))
      (node (ref "R7") (pin "2") (pinfunction "2_2") (pintype "passive"))
      (node (ref "U2") (pin "27") (pinfunction "VDDIO_REG_27") (pintype "output"))
      (node (ref "U2") (pin "8") (pinfunction "VDDH_REG_8") (pintype "output"))
    )
    (net (code "120") (name "X1D04") (class "Default")
      (node (ref "R46") (pin "1") (pinfunction "1_1") (pintype "passive"))
      (node (ref "U3") (pin "75") (pinfunction "X1D04_75") (pintype "bidirectional"))
    )
    (net (code "121") (name "X1D36") (class "Default")
      (node (ref "R48") (pin "1") (pinfunction "1_1") (pintype "passive"))
      (node (ref "U3") (pin "15") (pinfunction "X1D36_15") (pintype "bidirectional"))
    )
    (net (code "122") (name "X1D37") (class "Default")
      (node (ref "R47") (pin "1") (pinfunction "1_1") (pintype "passive"))
      (node (ref "U3") (pin "18") (pinfunction "X1D37_18") (pintype "bidirectional"))
    )
    (net (code "123") (name "XL_DN0") (class "Default")
      (node (ref "U3") (pin "9") (pinfunction "X0D41_9") (pintype "bidirectional"))
      (node (ref "X2") (pin "2") (pinfunction "XL_DN0_2") (pintype "bidirectional"))
    )
    (net (code "124") (name "XL_DN1") (class "Default")
      (node (ref "U3") (pin "8") (pinfunction "X0D40_8") (pintype "bidirectional"))
      (node (ref "X2") (pin "1") (pinfunction "XL_DN1_1") (pintype "bidirectional"))
    )
    (net (code "125") (name "XL_UP0") (class "Default")
      (node (ref "R24") (pin "2") (pinfunction "2_2") (pintype "passive"))
      (node (ref "X2") (pin "3") (pinfunction "XL_UP0_3") (pintype "bidirectional"))
    )
    (net (code "126") (name "XL_UP1") (class "Default")
      (node (ref "R25") (pin "2") (pinfunction "2_2") (pintype "passive"))
      (node (ref "X2") (pin "4") (pinfunction "XL_UP1_4") (pintype "bidirectional"))
    )
    (net (code "127") (name "XSYS_RST_N") (class "Default")
      (node (ref "R36") (pin "1") (pinfunction "1_1") (pintype "passive"))
      (node (ref "U5") (pin "3") (pinfunction "A2_3") (pintype "input"))
      (node (ref "X2") (pin "6") (pinfunction "~{XSYS_RESET}_6") (pintype "bidirectional"))
    )
    (net (code "128") (name "unconnected-(U2-CLK_25M-Pad23)") (class "Default")
      (node (ref "U2") (pin "23") (pinfunction "CLK_25M_23") (pintype "output"))
    )
    (net (code "129") (name "unconnected-(U3-X0D08-Pad39)") (class "Default")
      (node (ref "U3") (pin "39") (pinfunction "X0D08_39") (pintype "bidirectional"))
    )
    (net (code "130") (name "unconnected-(U3-X0D09-Pad40)") (class "Default")
      (node (ref "U3") (pin "40") (pinfunction "X0D09_40") (pintype "bidirectional"))
    )
    (net (code "131") (name "unconnected-(U3-X0D11-Pad32)") (class "Default")
      (node (ref "U3") (pin "32") (pinfunction "X0D11_32") (pintype "bidirectional"))
    )
    (net (code "132") (name "unconnected-(U3-X0D12-Pad62)") (class "Default")
      (node (ref "U3") (pin "62") (pinfunction "X0D12_62") (pintype "bidirectional"))
    )
    (net (code "133") (name "unconnected-(U3-X0D14-Pad57)") (class "Default")
      (node (ref "U3") (pin "57") (pinfunction "X0D14_57") (pintype "bidirectional"))
    )
    (net (code "134") (name "unconnected-(U3-X0D15-Pad58)") (class "Default")
      (node (ref "U3") (pin "58") (pinfunction "X0D15_58") (pintype "bidirectional"))
    )
    (net (code "135") (name "unconnected-(U3-X0D16-Pad68)") (class "Default")
      (node (ref "U3") (pin "68") (pinfunction "X0D16_68") (pintype "bidirectional"))
    )
    (net (code "136") (name "unconnected-(U3-X0D17-Pad69)") (class "Default")
      (node (ref "U3") (pin "69") (pinfunction "X0D17_69") (pintype "bidirectional"))
    )
    (net (code "137") (name "unconnected-(U3-X0D18-Pad70)") (class "Default")
      (node (ref "U3") (pin "70") (pinfunction "X0D18_70") (pintype "bidirectional"))
    )
    (net (code "138") (name "unconnected-(U3-X0D19-Pad71)") (class "Default")
      (node (ref "U3") (pin "71") (pinfunction "X0D19_71") (pintype "bidirectional"))
    )
    (net (code "139") (name "unconnected-(U3-X0D20-Pad59)") (class "Default")
      (node (ref "U3") (pin "59") (pinfunction "X0D20_59") (pintype "bidirectional"))
    )
    (net (code "140") (name "unconnected-(U3-X0D21-Pad61)") (class "Default")
      (node (ref "U3") (pin "61") (pinfunction "X0D21_61") (pintype "bidirectional"))
    )
    (net (code "141") (name "unconnected-(U3-X0D26-Pad93)") (class "Default")
      (node (ref "U3") (pin "93") (pinfunction "X0D26_93") (pintype "bidirectional"))
    )
    (net (code "142") (name "unconnected-(U3-X0D27-Pad94)") (class "Default")
      (node (ref "U3") (pin "94") (pinfunction "X0D27_94") (pintype "bidirectional"))
    )
    (net (code "143") (name "unconnected-(U3-X0D28-Pad96)") (class "Default")
      (node (ref "U3") (pin "96") (pinfunction "X0D28_96") (pintype "bidirectional"))
    )
    (net (code "144") (name "unconnected-(U3-X0D29-Pad98)") (class "Default")
      (node (ref "U3") (pin "98") (pinfunction "X0D29_98") (pintype "bidirectional"))
    )
    (net (code "145") (name "unconnected-(U3-X0D31-Pad100)") (class "Default")
      (node (ref "U3") (pin "100") (pinfunction "X0D31_100") (pintype "bidirectional"))
    )
    (net (code "146") (name "unconnected-(U3-X0D33-Pad97)") (class "Default")
      (node (ref "U3") (pin "97") (pinfunction "X0D33_97") (pintype "bidirectional"))
    )
    (net (code "147") (name "unconnected-(U3-X0D36-Pad3)") (class "Default")
      (node (ref "U3") (pin "3") (pinfunction "X0D36_3") (pintype "bidirectional"))
    )
    (net (code "148") (name "unconnected-(U3-X0D37-Pad4)") (class "Default")
      (node (ref "U3") (pin "4") (pinfunction "X0D37_4") (pintype "bidirectional"))
    )
    (net (code "149") (name "unconnected-(U3-X0D38-Pad5)") (class "Default")
      (node (ref "U3") (pin "5") (pinfunction "X0D38_5") (pintype "bidirectional"))
    )
    (net (code "150") (name "unconnected-(U3-X0D39-Pad7)") (class "Default")
      (node (ref "U3") (pin "7") (pinfunction "X0D39_7") (pintype "bidirectional"))
    )
    (net (code "151") (name "unconnected-(U3-X1D00-Pad85)") (class "Default")
      (node (ref "U3") (pin "85") (pinfunction "X1D00_85") (pintype "bidirectional"))
    )
    (net (code "152") (name "unconnected-(U3-X1D01-Pad86)") (class "Default")
      (node (ref "U3") (pin "86") (pinfunction "X1D01_86") (pintype "bidirectional"))
    )
    (net (code "153") (name "unconnected-(U3-X1D05-Pad76)") (class "Default")
      (node (ref "U3") (pin "76") (pinfunction "X1D05_76") (pintype "bidirectional"))
    )
    (net (code "154") (name "unconnected-(U3-X1D06-Pad77)") (class "Default")
      (node (ref "U3") (pin "77") (pinfunction "X1D06_77") (pintype "bidirectional"))
    )
    (net (code "155") (name "unconnected-(U3-X1D07-Pad79)") (class "Default")
      (node (ref "U3") (pin "79") (pinfunction "X1D07_79") (pintype "bidirectional"))
    )
    (net (code "156") (name "unconnected-(U3-X1D08-Pad82)") (class "Default")
      (node (ref "U3") (pin "82") (pinfunction "X1D08_82") (pintype "bidirectional"))
    )
    (net (code "157") (name "unconnected-(U3-X1D09-Pad84)") (class "Default")
      (node (ref "U3") (pin "84") (pinfunction "X1D09_84") (pintype "bidirectional"))
    )
    (net (code "158") (name "unconnected-(U3-X1D14-Pad51)") (class "Default")
      (node (ref "U3") (pin "51") (pinfunction "X1D14_51") (pintype "bidirectional"))
    )
    (net (code "159") (name "unconnected-(U3-X1D15-Pad53)") (class "Default")
      (node (ref "U3") (pin "53") (pinfunction "X1D15_53") (pintype "bidirectional"))
    )
    (net (code "160") (name "unconnected-(U3-X1D16-Pad22)") (class "Default")
      (node (ref "U3") (pin "22") (pinfunction "X1D16_22") (pintype "bidirectional"))
    )
    (net (code "161") (name "unconnected-(U3-X1D17-Pad23)") (class "Default")
      (node (ref "U3") (pin "23") (pinfunction "X1D17_23") (pintype "bidirectional"))
    )
    (net (code "162") (name "unconnected-(U3-X1D18-Pad25)") (class "Default")
      (node (ref "U3") (pin "25") (pinfunction "X1D18_25") (pintype "bidirectional"))
    )
    (net (code "163") (name "unconnected-(U3-X1D19-Pad26)") (class "Default")
      (node (ref "U3") (pin "26") (pinfunction "X1D19_26") (pintype "bidirectional"))
    )
    (net (code "164") (name "unconnected-(U3-X1D20-Pad54)") (class "Default")
      (node (ref "U3") (pin "54") (pinfunction "X1D20_54") (pintype "bidirectional"))
    )
    (net (code "165") (name "unconnected-(U3-X1D21-Pad55)") (class "Default")
      (node (ref "U3") (pin "55") (pinfunction "X1D21_55") (pintype "bidirectional"))
    )
    (net (code "166") (name "unconnected-(U3-X1D38-Pad20)") (class "Default")
      (node (ref "U3") (pin "20") (pinfunction "X1D38_20") (pintype "bidirectional"))
    )
    (net (code "167") (name "unconnected-(U3-X1D39-Pad21)") (class "Default")
      (node (ref "U3") (pin "21") (pinfunction "X1D39_21") (pintype "bidirectional"))
    )
    (net (code "168") (name "unconnected-(U6-AUX_OUT-Pad4)") (class "Default")
      (node (ref "U6") (pin "4") (pinfunction "AUX_OUT_4") (pintype "bidirectional"))
    )
    (net (code "169") (name "unconnected-(U6-XTO-Pad6)") (class "Default")
      (node (ref "U6") (pin "6") (pinfunction "XTO_6") (pintype "bidirectional"))
    )
  )
)
